# RoboDiscovery-F4_V1_0.net
KiCad netlist of a schematic drawn in EAGLE
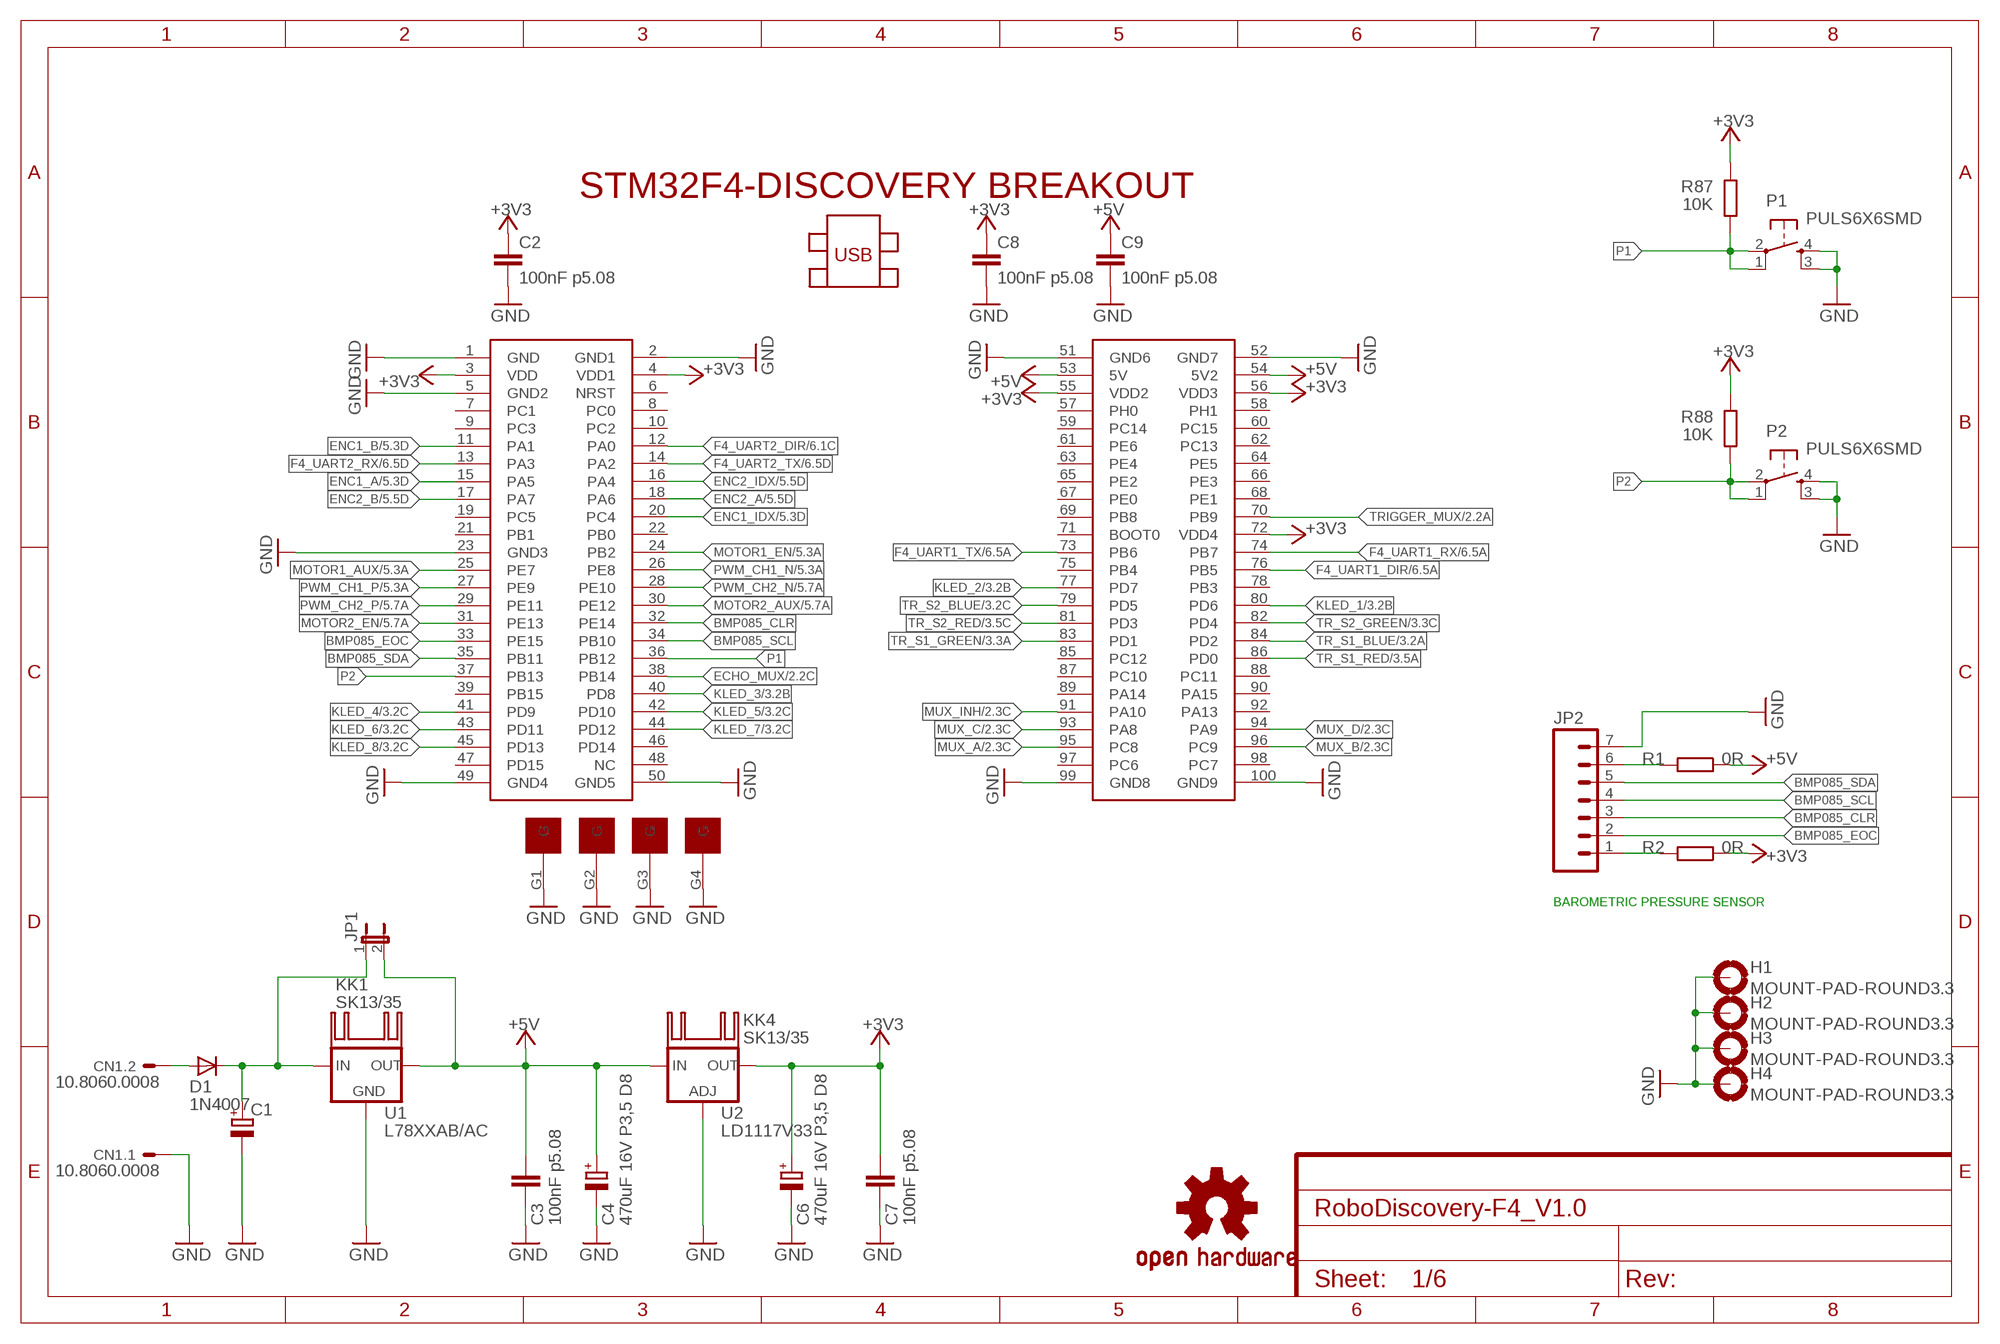
[diagram p0: schematic, sheet 1]
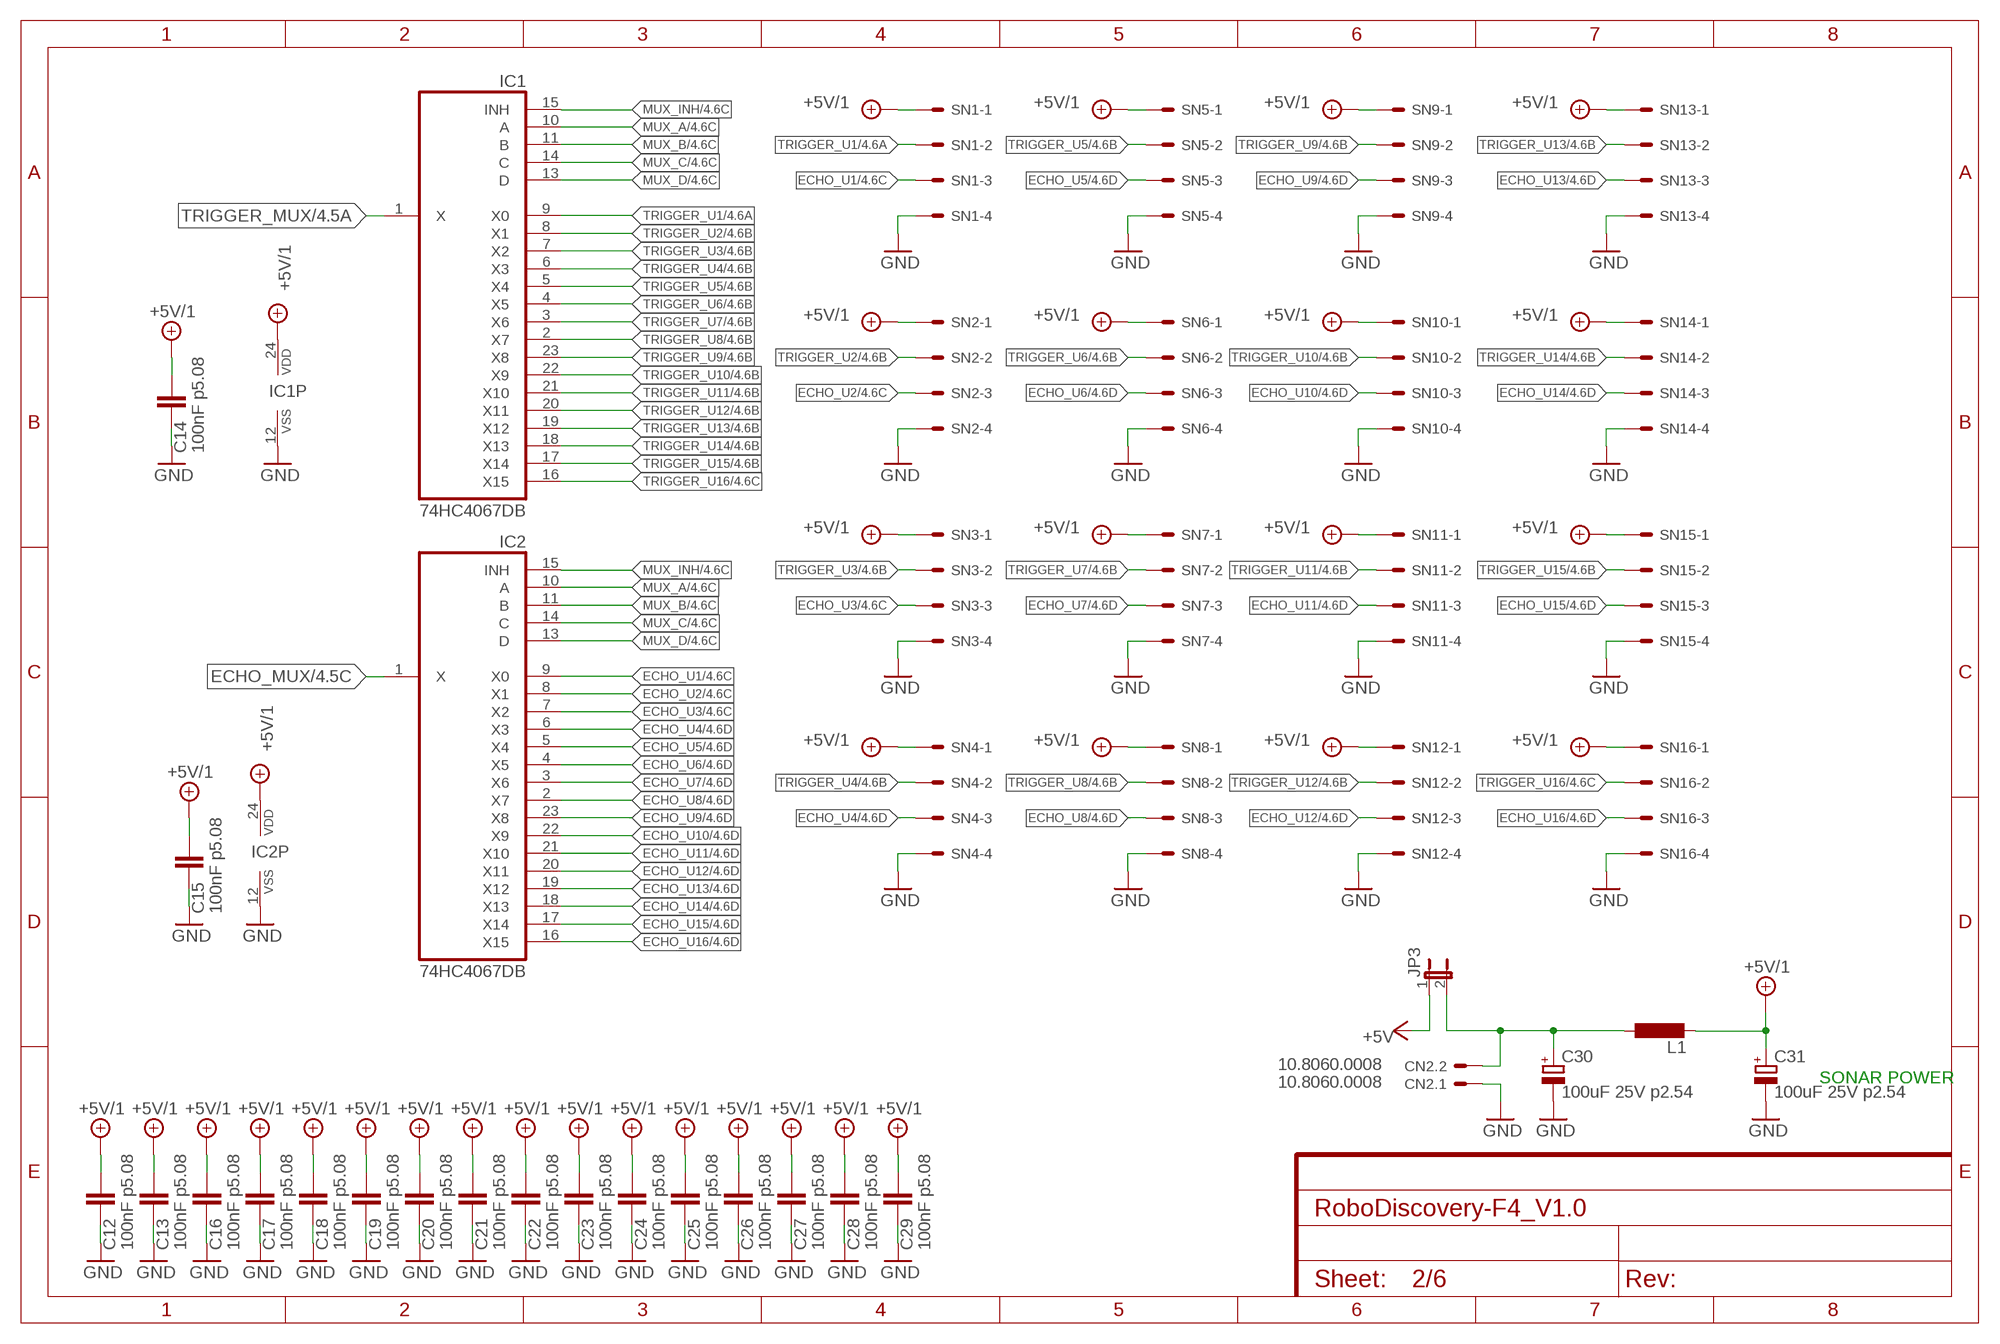
[diagram p1: schematic, sheet 2]
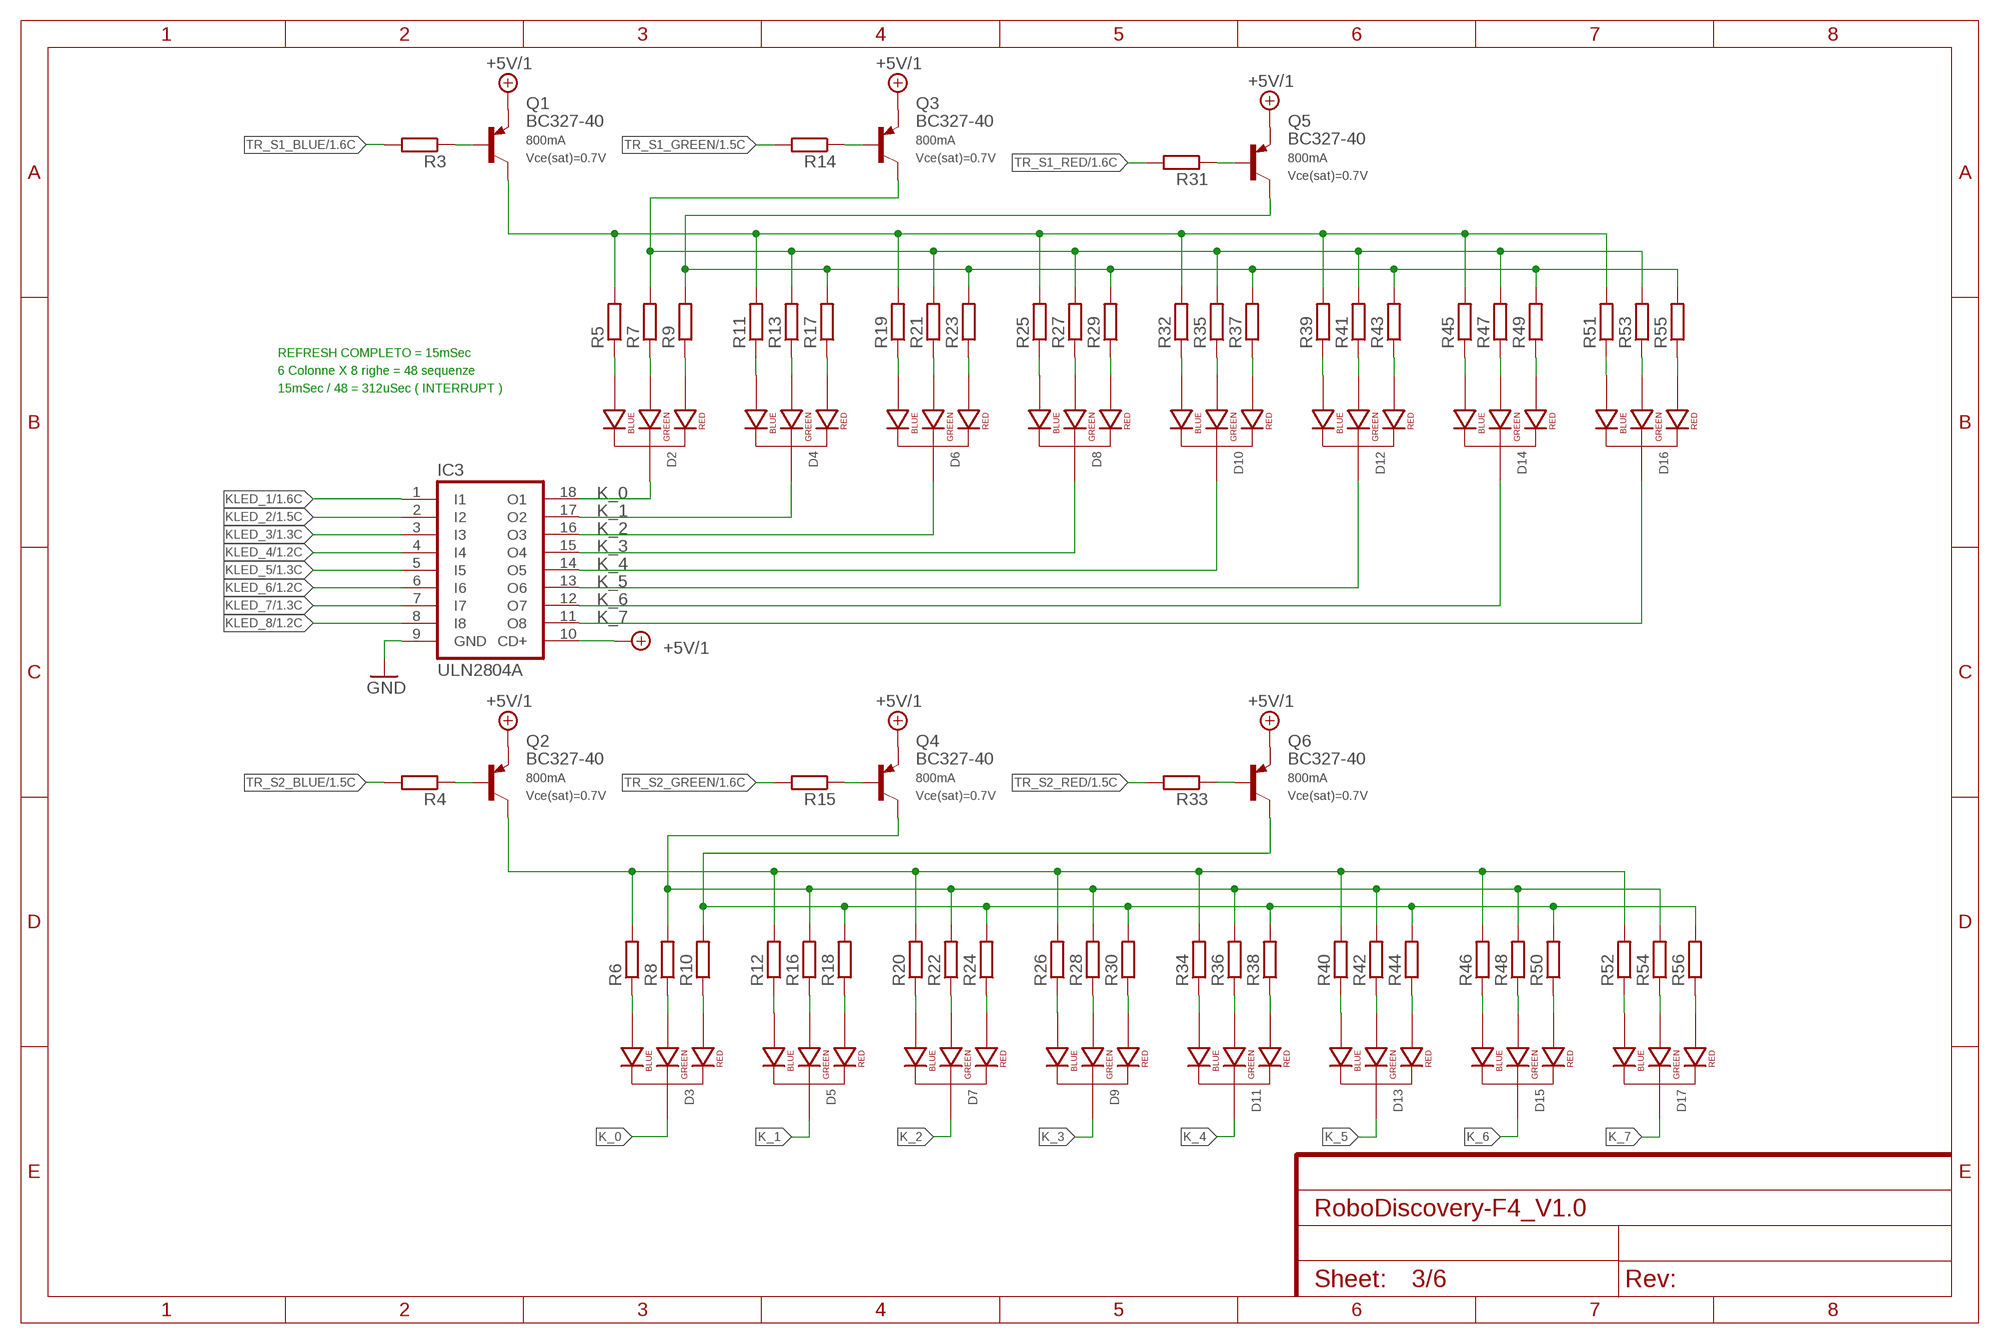
[diagram p2: schematic, sheet 3]
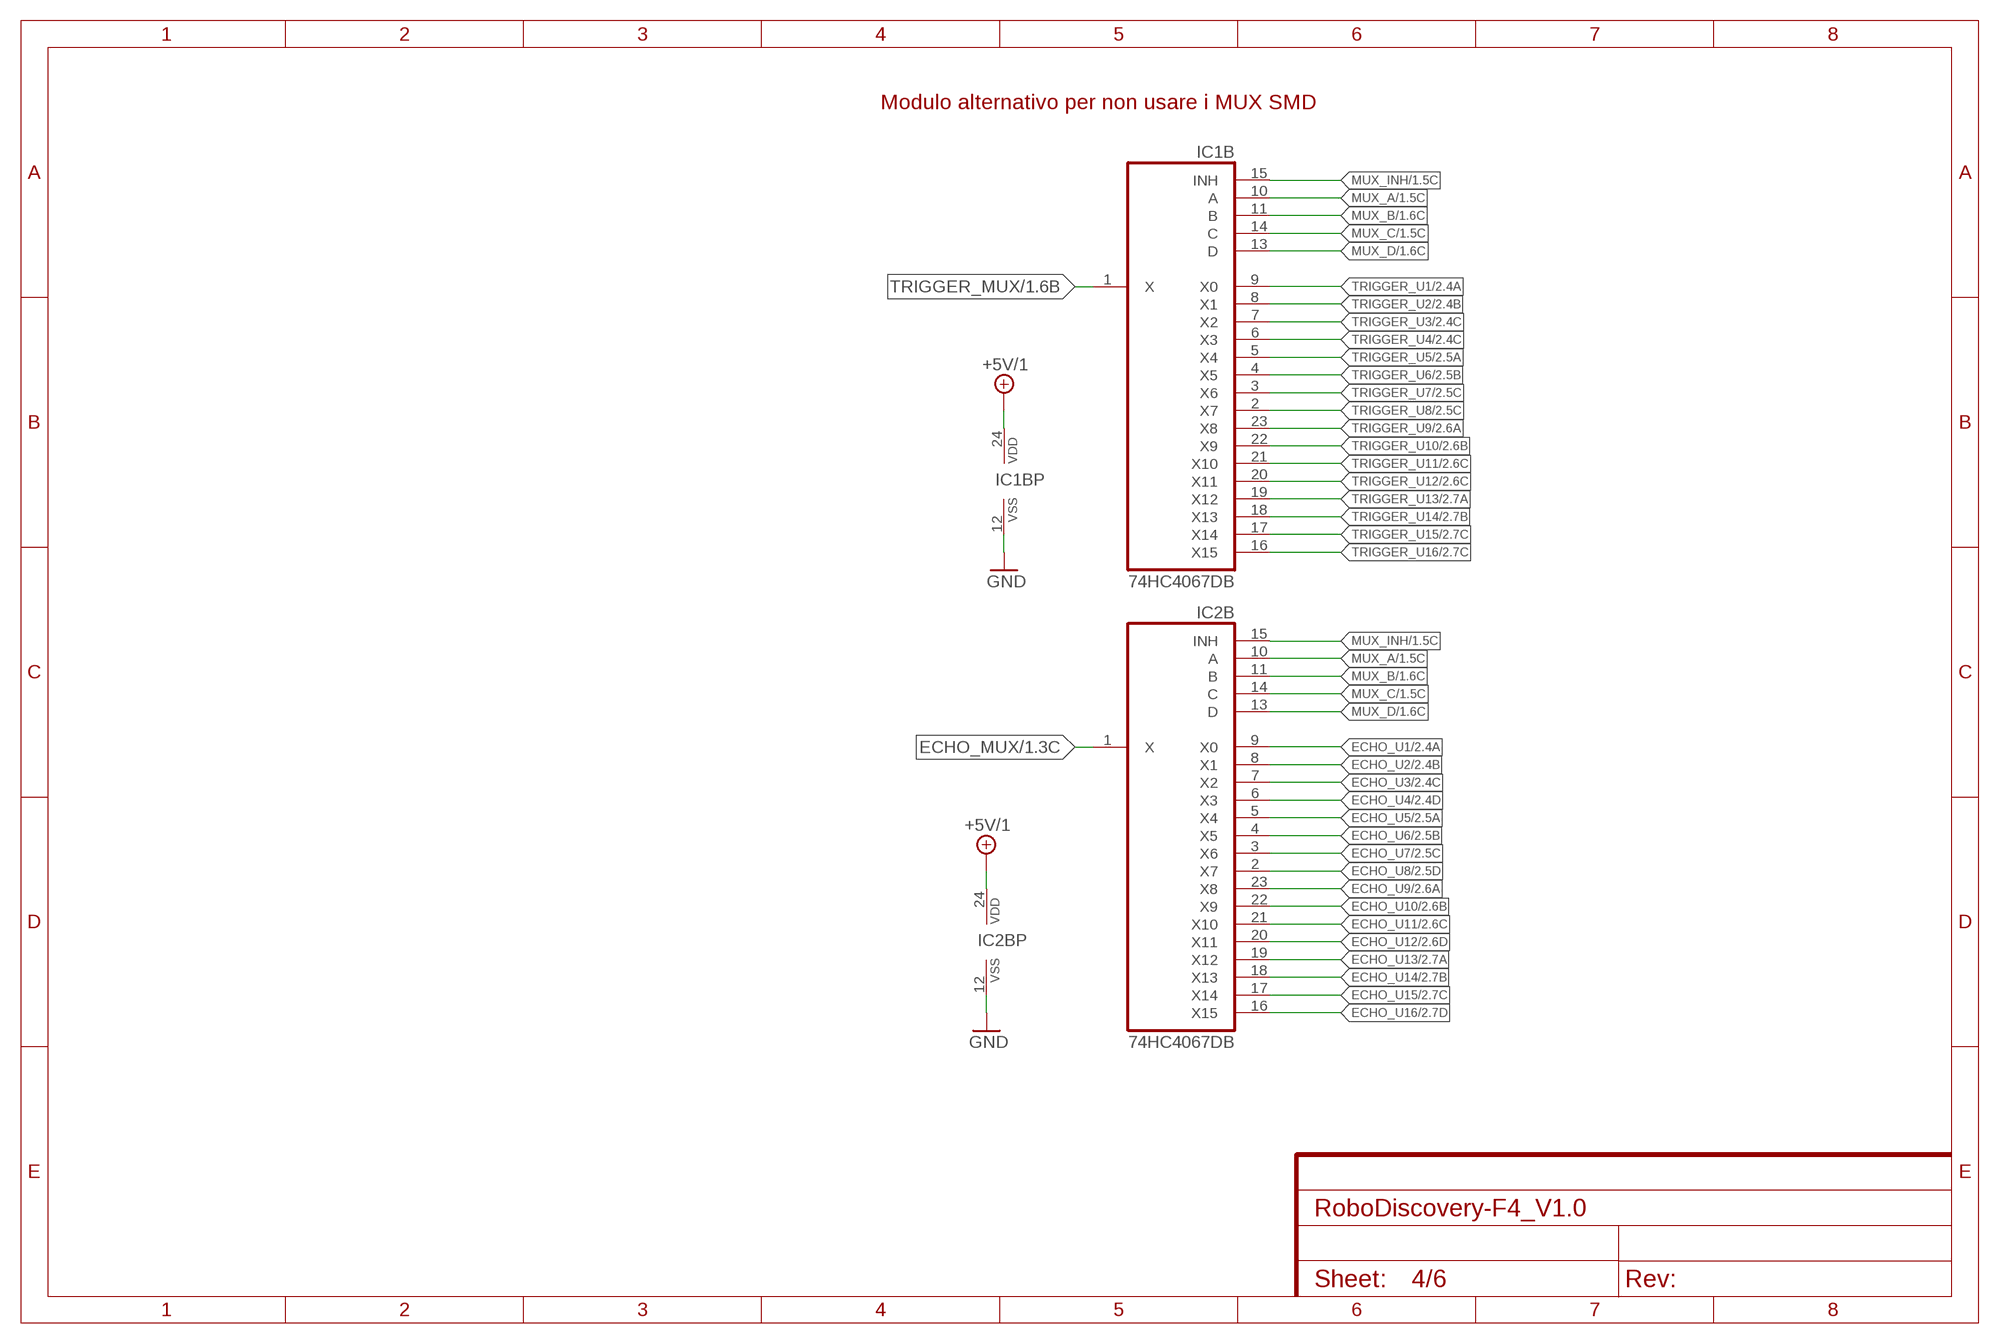
[diagram p3: schematic, sheet 4]
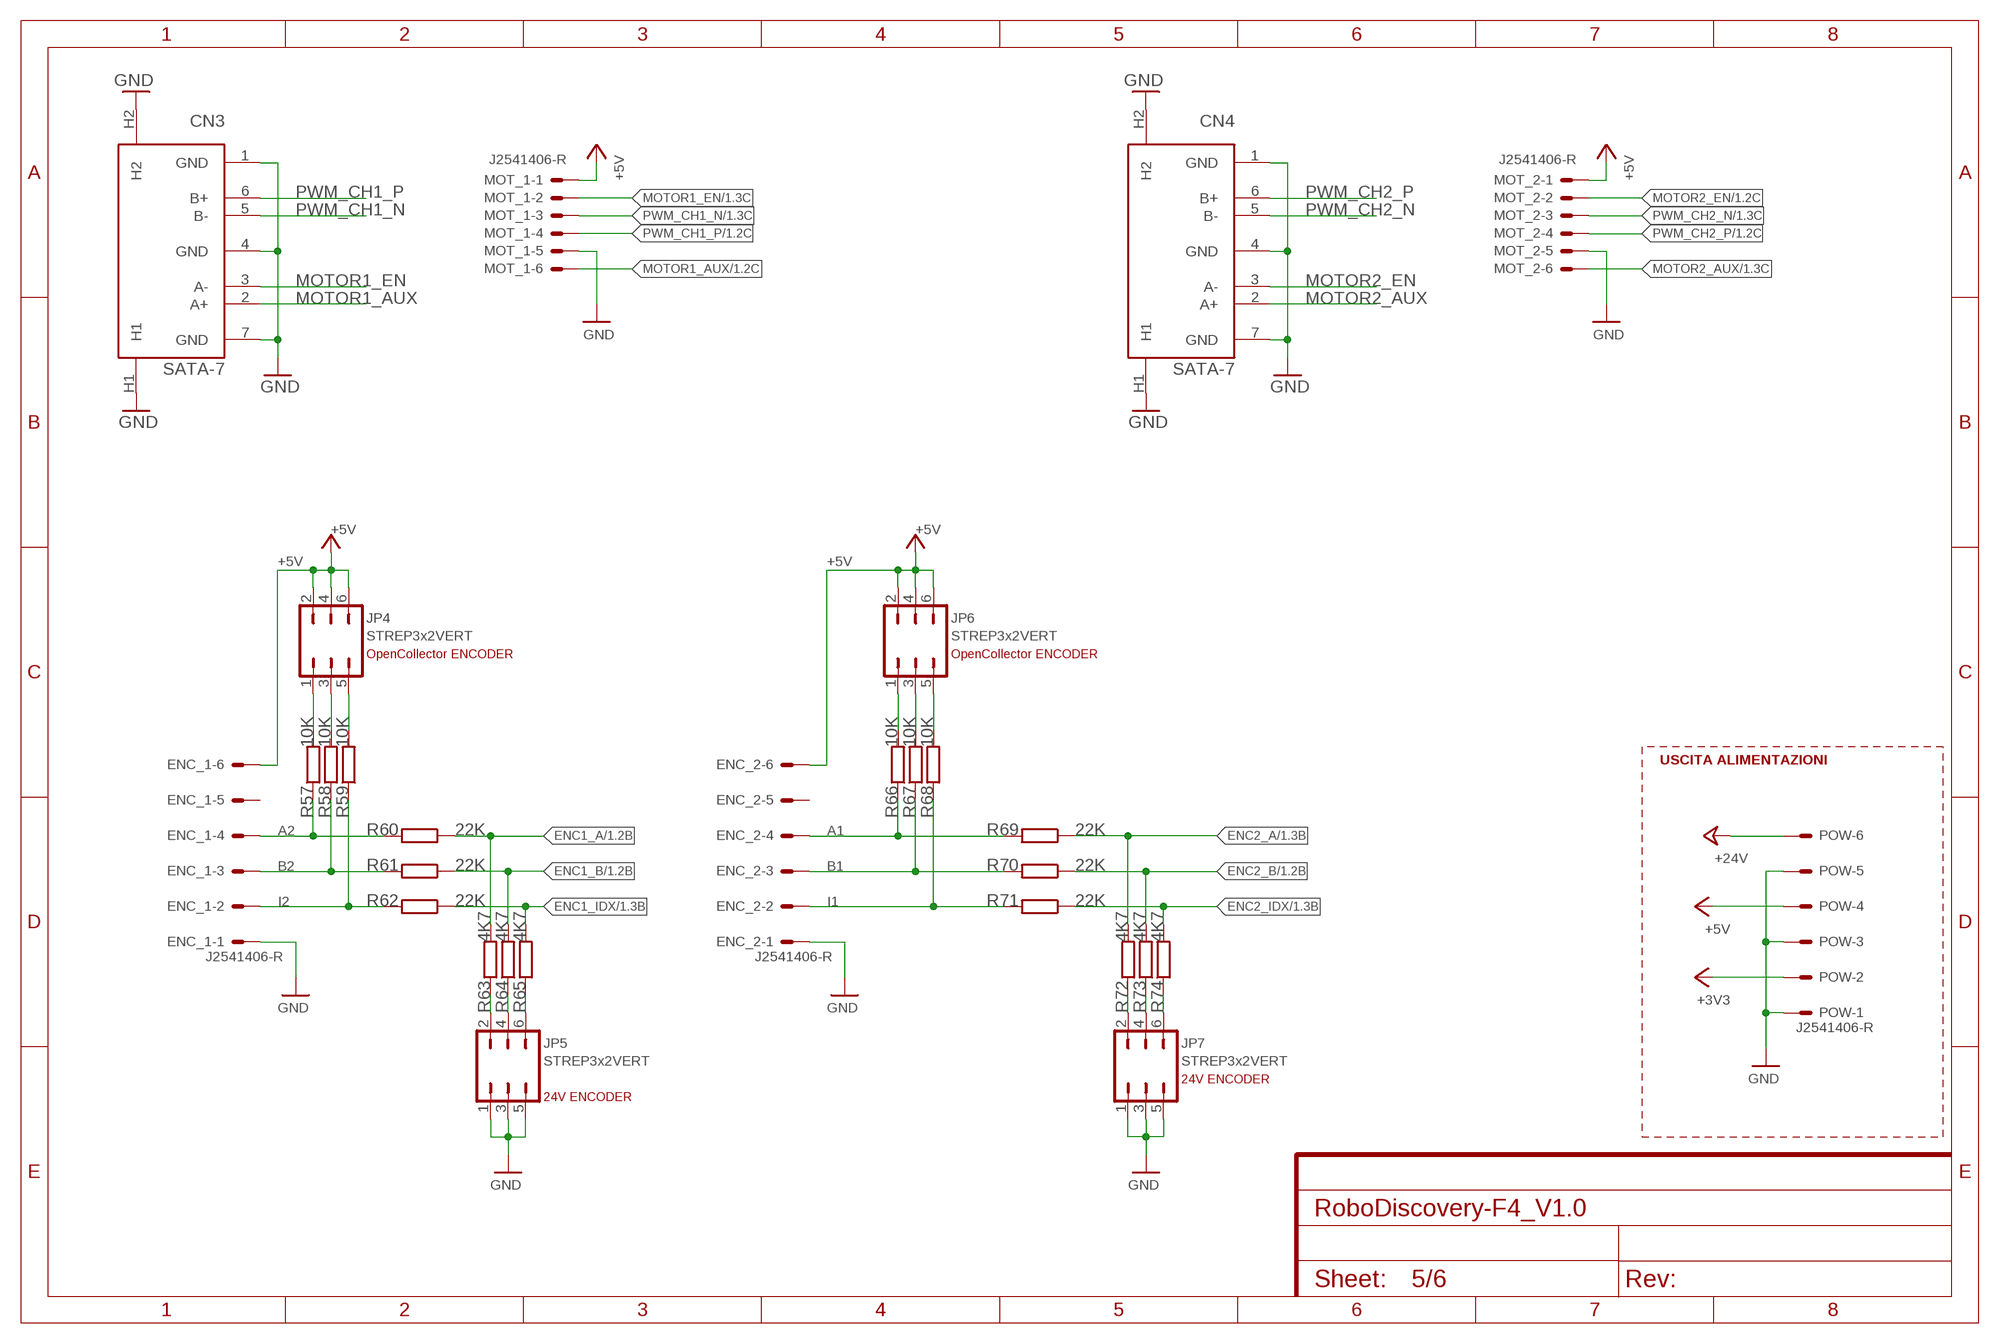
[diagram p4: schematic, sheet 5]
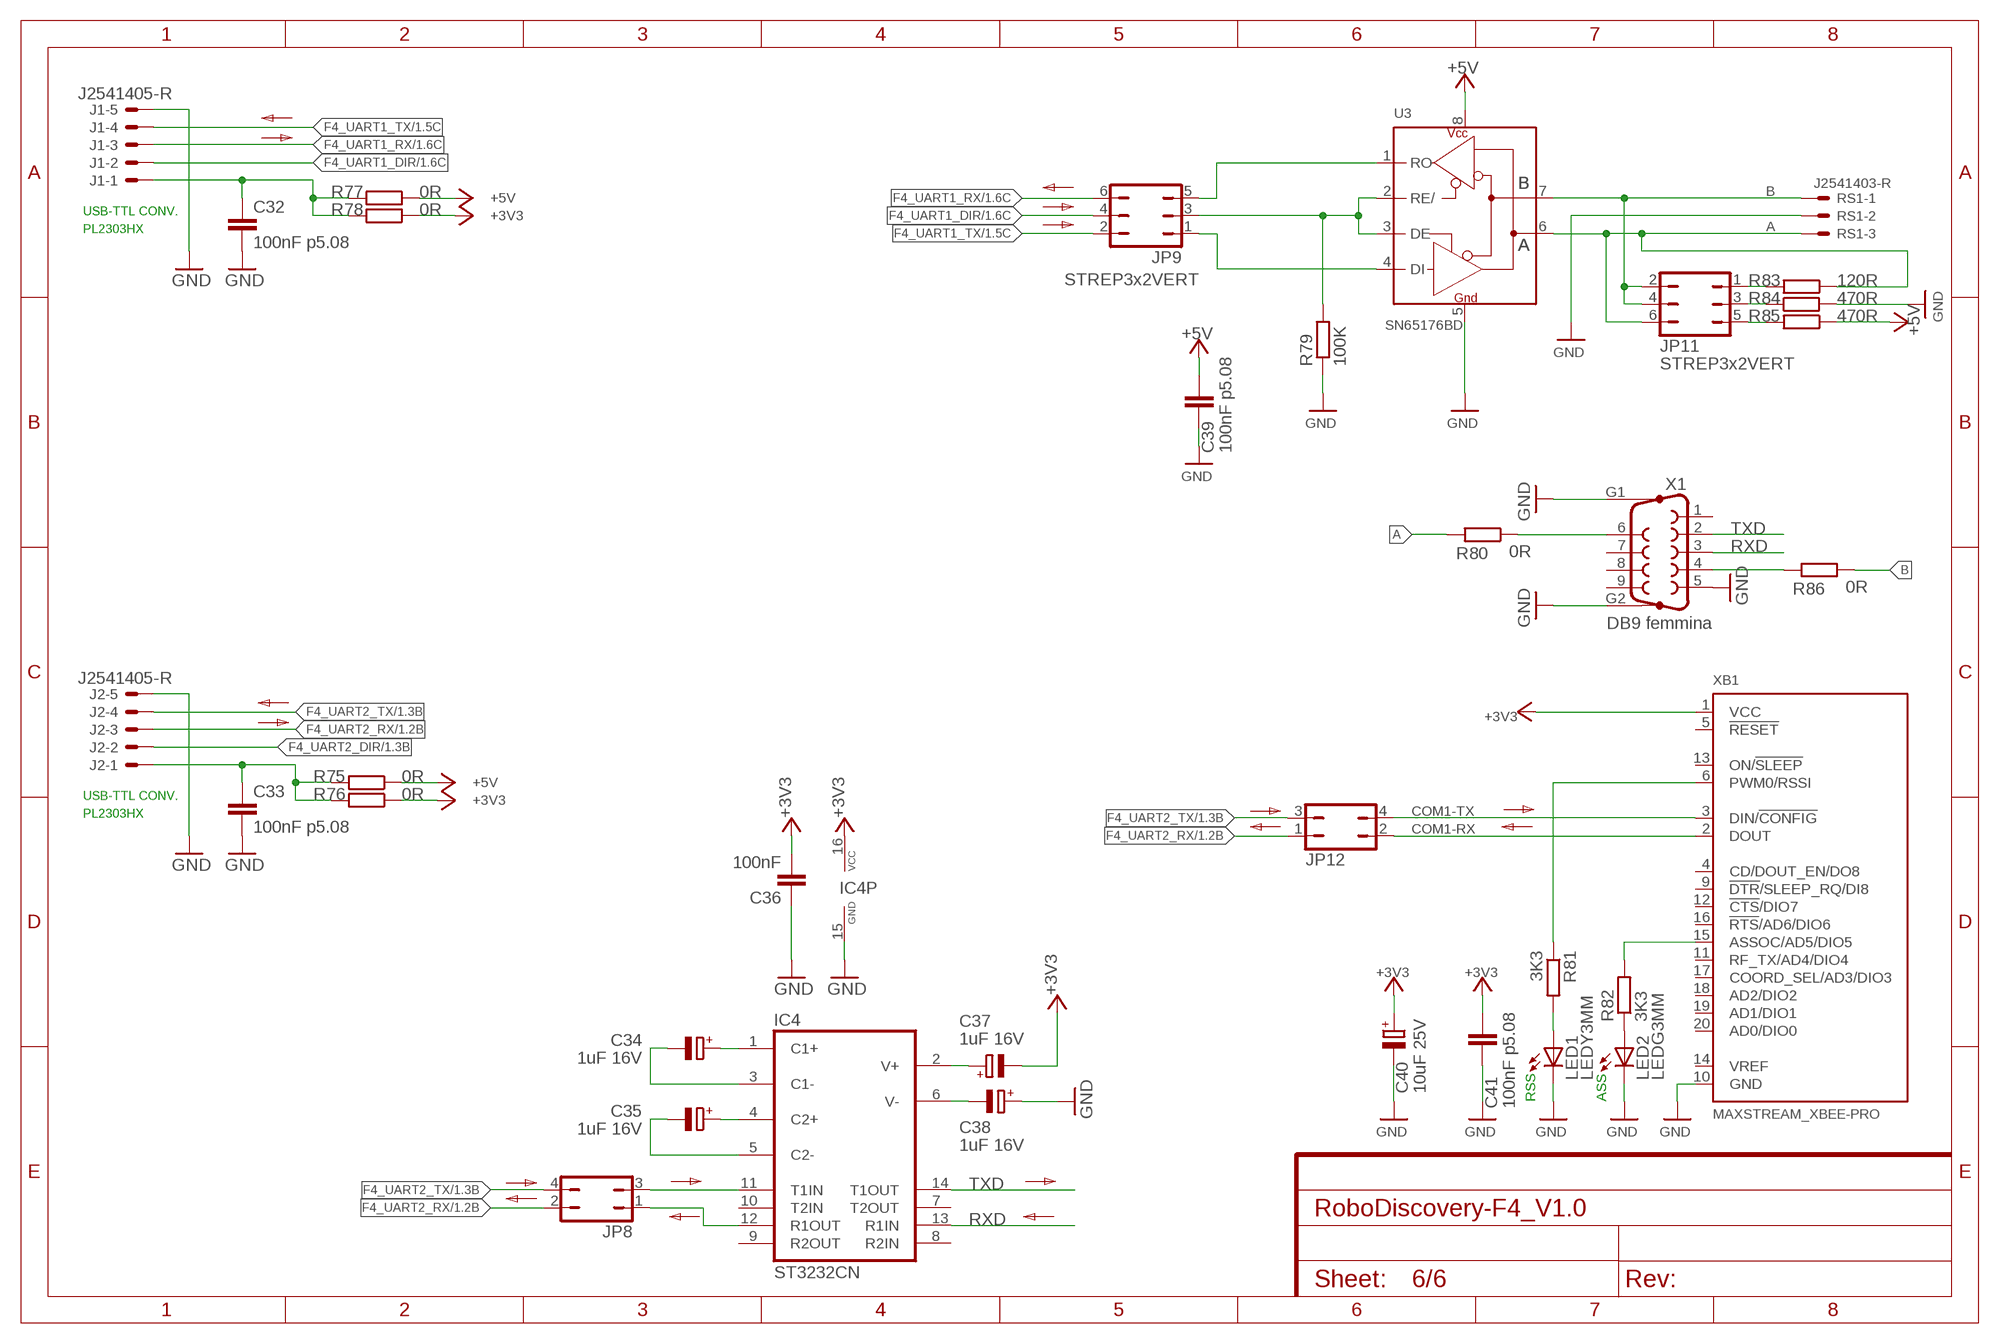
[diagram p5: schematic, sheet 6]

(export (version "E")
  (design (tool "Eeschema 10.0.6"))
  (components
    (comp (ref "D2")
      (value "LED-RGB-CC-THRUDIFFUSE")
      (footprint "eagle-import:LED-RGB-THRU")
      (libsource (lib "eagle-import") (part "LED-RGB-CC-THRUDIFFUSE"))
    )
    (comp (ref "D3")
      (value "LED-RGB-CC-THRUDIFFUSE")
      (footprint "eagle-import:LED-RGB-THRU")
      (libsource (lib "eagle-import") (part "LED-RGB-CC-THRUDIFFUSE"))
    )
    (comp (ref "D4")
      (value "LED-RGB-CC-THRUDIFFUSE")
      (footprint "eagle-import:LED-RGB-THRU")
      (libsource (lib "eagle-import") (part "LED-RGB-CC-THRUDIFFUSE"))
    )
    (comp (ref "D5")
      (value "LED-RGB-CC-THRUDIFFUSE")
      (footprint "eagle-import:LED-RGB-THRU")
      (libsource (lib "eagle-import") (part "LED-RGB-CC-THRUDIFFUSE"))
    )
    (comp (ref "D6")
      (value "LED-RGB-CC-THRUDIFFUSE")
      (footprint "eagle-import:LED-RGB-THRU")
      (libsource (lib "eagle-import") (part "LED-RGB-CC-THRUDIFFUSE"))
    )
    (comp (ref "D7")
      (value "LED-RGB-CC-THRUDIFFUSE")
      (footprint "eagle-import:LED-RGB-THRU")
      (libsource (lib "eagle-import") (part "LED-RGB-CC-THRUDIFFUSE"))
    )
    (comp (ref "D8")
      (value "LED-RGB-CC-THRUDIFFUSE")
      (footprint "eagle-import:LED-RGB-THRU")
      (libsource (lib "eagle-import") (part "LED-RGB-CC-THRUDIFFUSE"))
    )
    (comp (ref "D9")
      (value "LED-RGB-CC-THRUDIFFUSE")
      (footprint "eagle-import:LED-RGB-THRU")
      (libsource (lib "eagle-import") (part "LED-RGB-CC-THRUDIFFUSE"))
    )
    (comp (ref "D10")
      (value "LED-RGB-CC-THRUDIFFUSE")
      (footprint "eagle-import:LED-RGB-THRU")
      (libsource (lib "eagle-import") (part "LED-RGB-CC-THRUDIFFUSE"))
    )
    (comp (ref "D11")
      (value "LED-RGB-CC-THRUDIFFUSE")
      (footprint "eagle-import:LED-RGB-THRU")
      (libsource (lib "eagle-import") (part "LED-RGB-CC-THRUDIFFUSE"))
    )
    (comp (ref "D12")
      (value "LED-RGB-CC-THRUDIFFUSE")
      (footprint "eagle-import:LED-RGB-THRU")
      (libsource (lib "eagle-import") (part "LED-RGB-CC-THRUDIFFUSE"))
    )
    (comp (ref "D13")
      (value "LED-RGB-CC-THRUDIFFUSE")
      (footprint "eagle-import:LED-RGB-THRU")
      (libsource (lib "eagle-import") (part "LED-RGB-CC-THRUDIFFUSE"))
    )
    (comp (ref "D14")
      (value "LED-RGB-CC-THRUDIFFUSE")
      (footprint "eagle-import:LED-RGB-THRU")
      (libsource (lib "eagle-import") (part "LED-RGB-CC-THRUDIFFUSE"))
    )
    (comp (ref "D15")
      (value "LED-RGB-CC-THRUDIFFUSE")
      (footprint "eagle-import:LED-RGB-THRU")
      (libsource (lib "eagle-import") (part "LED-RGB-CC-THRUDIFFUSE"))
    )
    (comp (ref "D16")
      (value "LED-RGB-CC-THRUDIFFUSE")
      (footprint "eagle-import:LED-RGB-THRU")
      (libsource (lib "eagle-import") (part "LED-RGB-CC-THRUDIFFUSE"))
    )
    (comp (ref "D17")
      (value "LED-RGB-CC-THRUDIFFUSE")
      (footprint "eagle-import:LED-RGB-THRU")
      (libsource (lib "eagle-import") (part "LED-RGB-CC-THRUDIFFUSE"))
    )
    (comp (ref "IC3")
      (value "ULN2804A")
      (footprint "eagle-import:DIL18")
      (libsource (lib "eagle-import") (part "ULN2804A"))
    )
    (comp (ref "Q1")
      (value "BC327-40")
      (footprint "eagle-import:TO92-EBC")
      (fields (field (name "I") "800mA") (field (name "VCESAT") "Vce(sat)=0.7V"))
      (libsource (lib "eagle-import") (part "BC327-40"))
    )
    (comp (ref "Q2")
      (value "BC327-40")
      (footprint "eagle-import:TO92-EBC")
      (fields (field (name "I") "800mA") (field (name "VCESAT") "Vce(sat)=0.7V"))
      (libsource (lib "eagle-import") (part "BC327-40"))
    )
    (comp (ref "Q3")
      (value "BC327-40")
      (footprint "eagle-import:TO92-EBC")
      (fields (field (name "I") "800mA") (field (name "VCESAT") "Vce(sat)=0.7V"))
      (libsource (lib "eagle-import") (part "BC327-40"))
    )
    (comp (ref "Q4")
      (value "BC327-40")
      (footprint "eagle-import:TO92-EBC")
      (fields (field (name "I") "800mA") (field (name "VCESAT") "Vce(sat)=0.7V"))
      (libsource (lib "eagle-import") (part "BC327-40"))
    )
    (comp (ref "Q5")
      (value "BC327-40")
      (footprint "eagle-import:TO92-EBC")
      (fields (field (name "I") "800mA") (field (name "VCESAT") "Vce(sat)=0.7V"))
      (libsource (lib "eagle-import") (part "BC327-40"))
    )
    (comp (ref "Q6")
      (value "BC327-40")
      (footprint "eagle-import:TO92-EBC")
      (fields (field (name "I") "800mA") (field (name "VCESAT") "Vce(sat)=0.7V"))
      (libsource (lib "eagle-import") (part "BC327-40"))
    )
    (comp (ref "R3")
      (value "R-EU_0207/7")
      (footprint "eagle-import:0207_7")
      (libsource (lib "eagle-import") (part "R-EU_0207/7"))
    )
    (comp (ref "R4")
      (value "R-EU_0207/7")
      (footprint "eagle-import:0207_7")
      (libsource (lib "eagle-import") (part "R-EU_0207/7"))
    )
    (comp (ref "R5")
      (value "R-EU_0207/7")
      (footprint "eagle-import:0207_7")
      (libsource (lib "eagle-import") (part "R-EU_0207/7"))
    )
    (comp (ref "R6")
      (value "R-EU_0207/7")
      (footprint "eagle-import:0207_7")
      (libsource (lib "eagle-import") (part "R-EU_0207/7"))
    )
    (comp (ref "R7")
      (value "R-EU_0207/7")
      (footprint "eagle-import:0207_7")
      (libsource (lib "eagle-import") (part "R-EU_0207/7"))
    )
    (comp (ref "R8")
      (value "R-EU_0207/7")
      (footprint "eagle-import:0207_7")
      (libsource (lib "eagle-import") (part "R-EU_0207/7"))
    )
    (comp (ref "R9")
      (value "R-EU_0207/7")
      (footprint "eagle-import:0207_7")
      (libsource (lib "eagle-import") (part "R-EU_0207/7"))
    )
    (comp (ref "R10")
      (value "R-EU_0207/7")
      (footprint "eagle-import:0207_7")
      (libsource (lib "eagle-import") (part "R-EU_0207/7"))
    )
    (comp (ref "R11")
      (value "R-EU_0207/7")
      (footprint "eagle-import:0207_7")
      (libsource (lib "eagle-import") (part "R-EU_0207/7"))
    )
    (comp (ref "R12")
      (value "R-EU_0207/7")
      (footprint "eagle-import:0207_7")
      (libsource (lib "eagle-import") (part "R-EU_0207/7"))
    )
    (comp (ref "R13")
      (value "R-EU_0207/7")
      (footprint "eagle-import:0207_7")
      (libsource (lib "eagle-import") (part "R-EU_0207/7"))
    )
    (comp (ref "R14")
      (value "R-EU_0207/7")
      (footprint "eagle-import:0207_7")
      (libsource (lib "eagle-import") (part "R-EU_0207/7"))
    )
    (comp (ref "R15")
      (value "R-EU_0207/7")
      (footprint "eagle-import:0207_7")
      (libsource (lib "eagle-import") (part "R-EU_0207/7"))
    )
    (comp (ref "R16")
      (value "R-EU_0207/7")
      (footprint "eagle-import:0207_7")
      (libsource (lib "eagle-import") (part "R-EU_0207/7"))
    )
    (comp (ref "R17")
      (value "R-EU_0207/7")
      (footprint "eagle-import:0207_7")
      (libsource (lib "eagle-import") (part "R-EU_0207/7"))
    )
    (comp (ref "R18")
      (value "R-EU_0207/7")
      (footprint "eagle-import:0207_7")
      (libsource (lib "eagle-import") (part "R-EU_0207/7"))
    )
    (comp (ref "R19")
      (value "R-EU_0207/7")
      (footprint "eagle-import:0207_7")
      (libsource (lib "eagle-import") (part "R-EU_0207/7"))
    )
    (comp (ref "R20")
      (value "R-EU_0207/7")
      (footprint "eagle-import:0207_7")
      (libsource (lib "eagle-import") (part "R-EU_0207/7"))
    )
    (comp (ref "R21")
      (value "R-EU_0207/7")
      (footprint "eagle-import:0207_7")
      (libsource (lib "eagle-import") (part "R-EU_0207/7"))
    )
    (comp (ref "R22")
      (value "R-EU_0207/7")
      (footprint "eagle-import:0207_7")
      (libsource (lib "eagle-import") (part "R-EU_0207/7"))
    )
    (comp (ref "R23")
      (value "R-EU_0207/7")
      (footprint "eagle-import:0207_7")
      (libsource (lib "eagle-import") (part "R-EU_0207/7"))
    )
    (comp (ref "R24")
      (value "R-EU_0207/7")
      (footprint "eagle-import:0207_7")
      (libsource (lib "eagle-import") (part "R-EU_0207/7"))
    )
    (comp (ref "R25")
      (value "R-EU_0207/7")
      (footprint "eagle-import:0207_7")
      (libsource (lib "eagle-import") (part "R-EU_0207/7"))
    )
    (comp (ref "R26")
      (value "R-EU_0207/7")
      (footprint "eagle-import:0207_7")
      (libsource (lib "eagle-import") (part "R-EU_0207/7"))
    )
    (comp (ref "R27")
      (value "R-EU_0207/7")
      (footprint "eagle-import:0207_7")
      (libsource (lib "eagle-import") (part "R-EU_0207/7"))
    )
    (comp (ref "R28")
      (value "R-EU_0207/7")
      (footprint "eagle-import:0207_7")
      (libsource (lib "eagle-import") (part "R-EU_0207/7"))
    )
    (comp (ref "R29")
      (value "R-EU_0207/7")
      (footprint "eagle-import:0207_7")
      (libsource (lib "eagle-import") (part "R-EU_0207/7"))
    )
    (comp (ref "R30")
      (value "R-EU_0207/7")
      (footprint "eagle-import:0207_7")
      (libsource (lib "eagle-import") (part "R-EU_0207/7"))
    )
    (comp (ref "R31")
      (value "R-EU_0207/7")
      (footprint "eagle-import:0207_7")
      (libsource (lib "eagle-import") (part "R-EU_0207/7"))
    )
    (comp (ref "R32")
      (value "R-EU_0207/7")
      (footprint "eagle-import:0207_7")
      (libsource (lib "eagle-import") (part "R-EU_0207/7"))
    )
    (comp (ref "R33")
      (value "R-EU_0207/7")
      (footprint "eagle-import:0207_7")
      (libsource (lib "eagle-import") (part "R-EU_0207/7"))
    )
    (comp (ref "R34")
      (value "R-EU_0207/7")
      (footprint "eagle-import:0207_7")
      (libsource (lib "eagle-import") (part "R-EU_0207/7"))
    )
    (comp (ref "R35")
      (value "R-EU_0207/7")
      (footprint "eagle-import:0207_7")
      (libsource (lib "eagle-import") (part "R-EU_0207/7"))
    )
    (comp (ref "R36")
      (value "R-EU_0207/7")
      (footprint "eagle-import:0207_7")
      (libsource (lib "eagle-import") (part "R-EU_0207/7"))
    )
    (comp (ref "R37")
      (value "R-EU_0207/7")
      (footprint "eagle-import:0207_7")
      (libsource (lib "eagle-import") (part "R-EU_0207/7"))
    )
    (comp (ref "R38")
      (value "R-EU_0207/7")
      (footprint "eagle-import:0207_7")
      (libsource (lib "eagle-import") (part "R-EU_0207/7"))
    )
    (comp (ref "R39")
      (value "R-EU_0207/7")
      (footprint "eagle-import:0207_7")
      (libsource (lib "eagle-import") (part "R-EU_0207/7"))
    )
    (comp (ref "R40")
      (value "R-EU_0207/7")
      (footprint "eagle-import:0207_7")
      (libsource (lib "eagle-import") (part "R-EU_0207/7"))
    )
    (comp (ref "R41")
      (value "R-EU_0207/7")
      (footprint "eagle-import:0207_7")
      (libsource (lib "eagle-import") (part "R-EU_0207/7"))
    )
    (comp (ref "R42")
      (value "R-EU_0207/7")
      (footprint "eagle-import:0207_7")
      (libsource (lib "eagle-import") (part "R-EU_0207/7"))
    )
    (comp (ref "R43")
      (value "R-EU_0207/7")
      (footprint "eagle-import:0207_7")
      (libsource (lib "eagle-import") (part "R-EU_0207/7"))
    )
    (comp (ref "R44")
      (value "R-EU_0207/7")
      (footprint "eagle-import:0207_7")
      (libsource (lib "eagle-import") (part "R-EU_0207/7"))
    )
    (comp (ref "R45")
      (value "R-EU_0207/7")
      (footprint "eagle-import:0207_7")
      (libsource (lib "eagle-import") (part "R-EU_0207/7"))
    )
    (comp (ref "R46")
      (value "R-EU_0207/7")
      (footprint "eagle-import:0207_7")
      (libsource (lib "eagle-import") (part "R-EU_0207/7"))
    )
    (comp (ref "R47")
      (value "R-EU_0207/7")
      (footprint "eagle-import:0207_7")
      (libsource (lib "eagle-import") (part "R-EU_0207/7"))
    )
    (comp (ref "R48")
      (value "R-EU_0207/7")
      (footprint "eagle-import:0207_7")
      (libsource (lib "eagle-import") (part "R-EU_0207/7"))
    )
    (comp (ref "R49")
      (value "R-EU_0207/7")
      (footprint "eagle-import:0207_7")
      (libsource (lib "eagle-import") (part "R-EU_0207/7"))
    )
    (comp (ref "R50")
      (value "R-EU_0207/7")
      (footprint "eagle-import:0207_7")
      (libsource (lib "eagle-import") (part "R-EU_0207/7"))
    )
    (comp (ref "R51")
      (value "R-EU_0207/7")
      (footprint "eagle-import:0207_7")
      (libsource (lib "eagle-import") (part "R-EU_0207/7"))
    )
    (comp (ref "R52")
      (value "R-EU_0207/7")
      (footprint "eagle-import:0207_7")
      (libsource (lib "eagle-import") (part "R-EU_0207/7"))
    )
    (comp (ref "R53")
      (value "R-EU_0207/7")
      (footprint "eagle-import:0207_7")
      (libsource (lib "eagle-import") (part "R-EU_0207/7"))
    )
    (comp (ref "R54")
      (value "R-EU_0207/7")
      (footprint "eagle-import:0207_7")
      (libsource (lib "eagle-import") (part "R-EU_0207/7"))
    )
    (comp (ref "R55")
      (value "R-EU_0207/7")
      (footprint "eagle-import:0207_7")
      (libsource (lib "eagle-import") (part "R-EU_0207/7"))
    )
    (comp (ref "R56")
      (value "R-EU_0207/7")
      (footprint "eagle-import:0207_7")
      (libsource (lib "eagle-import") (part "R-EU_0207/7"))
    )
    (comp (ref "C1")
      (value "CPOL-EUE5-13")
      (footprint "eagle-import:E5-13")
      (libsource (lib "eagle-import") (part "CPOL-EUE5-13"))
    )
    (comp (ref "C2")
      (value "100nF p5.08")
      (footprint "eagle-import:C050-024X044")
      (libsource (lib "eagle-import") (part "C-EU050-024X044"))
    )
    (comp (ref "C3")
      (value "100nF p5.08")
      (footprint "eagle-import:C050-024X044")
      (libsource (lib "eagle-import") (part "C-EU050-024X044"))
    )
    (comp (ref "C4")
      (value "470uF 16V P3,5 D8")
      (footprint "eagle-import:E3,5-8")
      (libsource (lib "eagle-import") (part "CPOL-EUE3.5-8"))
    )
    (comp (ref "C6")
      (value "470uF 16V P3,5 D8")
      (footprint "eagle-import:E3,5-8")
      (libsource (lib "eagle-import") (part "CPOL-EUE3.5-8"))
    )
    (comp (ref "C7")
      (value "100nF p5.08")
      (footprint "eagle-import:C050-024X044")
      (libsource (lib "eagle-import") (part "C-EU050-024X044"))
    )
    (comp (ref "C8")
      (value "100nF p5.08")
      (footprint "eagle-import:C050-024X044")
      (libsource (lib "eagle-import") (part "C-EU050-024X044"))
    )
    (comp (ref "C9")
      (value "100nF p5.08")
      (footprint "eagle-import:C050-024X044")
      (libsource (lib "eagle-import") (part "C-EU050-024X044"))
    )
    (comp (ref "CN1")
      (value "10.8060.0008")
      (footprint "eagle-import:300-021-13_2P_5VE")
      (libsource (lib "eagle-import") (part "10.8060.0008"))
    )
    (comp (ref "D1")
      (value "1N4007")
      (footprint "eagle-import:D041-10")
      (libsource (lib "eagle-import") (part "1N4007"))
    )
    (comp (ref "DIS1")
      (value "STM32F4-DISCOVERY")
      (footprint "eagle-import:STM32F4-DISCOVERY")
      (libsource (lib "eagle-import") (part "STM32F4-DISCOVERY"))
    )
    (comp (ref "H1")
      (value "MOUNT-PAD-ROUND3.3")
      (footprint "eagle-import:3,3-PAD")
      (libsource (lib "eagle-import") (part "MOUNT-PAD-ROUND3.3"))
    )
    (comp (ref "H2")
      (value "MOUNT-PAD-ROUND3.3")
      (footprint "eagle-import:3,3-PAD")
      (libsource (lib "eagle-import") (part "MOUNT-PAD-ROUND3.3"))
    )
    (comp (ref "H3")
      (value "MOUNT-PAD-ROUND3.3")
      (footprint "eagle-import:3,3-PAD")
      (libsource (lib "eagle-import") (part "MOUNT-PAD-ROUND3.3"))
    )
    (comp (ref "H4")
      (value "MOUNT-PAD-ROUND3.3")
      (footprint "eagle-import:3,3-PAD")
      (libsource (lib "eagle-import") (part "MOUNT-PAD-ROUND3.3"))
    )
    (comp (ref "JP1")
      (value "JP1E")
      (footprint "eagle-import:JP1")
      (libsource (lib "eagle-import") (part "JP1E"))
    )
    (comp (ref "JP2")
      (value "M07LONGPADS")
      (footprint "eagle-import:1X07_LONGPADS")
      (libsource (lib "eagle-import") (part "M07LONGPADS"))
    )
    (comp (ref "KK1")
      (value "SK13/35")
      (footprint "eagle-import:SK13_35")
      (libsource (lib "eagle-import") (part "SK13/35"))
    )
    (comp (ref "KK4")
      (value "SK13/35")
      (footprint "eagle-import:SK13_35")
      (libsource (lib "eagle-import") (part "SK13/35"))
    )
    (comp (ref "LOGO1")
      (value "OSHW-LOGOM")
      (footprint "eagle-import:OSHW-LOGO-M")
      (libsource (lib "eagle-import") (part "OSHW-LOGOM"))
    )
    (comp (ref "P1")
      (value "PULS6X6SMD")
      (footprint "eagle-import:PULS6X6SMD")
      (libsource (lib "eagle-import") (part "PULS6X6SMD"))
    )
    (comp (ref "P2")
      (value "PULS6X6SMD")
      (footprint "eagle-import:PULS6X6SMD")
      (libsource (lib "eagle-import") (part "PULS6X6SMD"))
    )
    (comp (ref "R1")
      (value "0R")
      (footprint "eagle-import:0207_7")
      (libsource (lib "eagle-import") (part "R-EU_0207/7"))
    )
    (comp (ref "R2")
      (value "0R")
      (footprint "eagle-import:0207_7")
      (libsource (lib "eagle-import") (part "R-EU_0207/7"))
    )
    (comp (ref "R87")
      (value "10K")
      (footprint "eagle-import:0207_7")
      (libsource (lib "eagle-import") (part "R-EU_0207/7"))
    )
    (comp (ref "R88")
      (value "10K")
      (footprint "eagle-import:0207_7")
      (libsource (lib "eagle-import") (part "R-EU_0207/7"))
    )
    (comp (ref "U1")
      (value "L78XXAB/AC")
      (footprint "eagle-import:78XXL")
      (libsource (lib "eagle-import") (part "L78XXAB/AC"))
    )
    (comp (ref "U2")
      (value "LD1117V33")
      (footprint "eagle-import:317TL")
      (libsource (lib "eagle-import") (part "LM317TL"))
    )
    (comp (ref "IC1B")
      (value "74HC4067DB")
      (footprint "eagle-import:DIL24-6")
      (libsource (lib "eagle-import") (part "4067N"))
    )
    (comp (ref "IC2B")
      (value "74HC4067DB")
      (footprint "eagle-import:DIL24-6")
      (libsource (lib "eagle-import") (part "4067N"))
    )
    (comp (ref "C32")
      (value "100nF p5.08")
      (footprint "eagle-import:C050-024X044")
      (libsource (lib "eagle-import") (part "C-EU050-024X044"))
    )
    (comp (ref "C33")
      (value "100nF p5.08")
      (footprint "eagle-import:C050-024X044")
      (libsource (lib "eagle-import") (part "C-EU050-024X044"))
    )
    (comp (ref "C34")
      (value "1uF 16V")
      (footprint "eagle-import:E2,5-5")
      (libsource (lib "eagle-import") (part "CPOL-EUE2.5-5"))
    )
    (comp (ref "C35")
      (value "1uF 16V")
      (footprint "eagle-import:E2,5-5")
      (libsource (lib "eagle-import") (part "CPOL-EUE2.5-5"))
    )
    (comp (ref "C36")
      (value "100nF")
      (footprint "eagle-import:C025-025X050")
      (libsource (lib "eagle-import") (part "C-EU025-025X050"))
    )
    (comp (ref "C37")
      (value "1uF 16V")
      (footprint "eagle-import:E2,5-5")
      (libsource (lib "eagle-import") (part "CPOL-EUE2.5-5"))
    )
    (comp (ref "C38")
      (value "1uF 16V")
      (footprint "eagle-import:E2,5-5")
      (libsource (lib "eagle-import") (part "CPOL-EUE2.5-5"))
    )
    (comp (ref "C39")
      (value "100nF p5.08")
      (footprint "eagle-import:C050-024X044")
      (libsource (lib "eagle-import") (part "C-EU050-024X044"))
    )
    (comp (ref "C40")
      (value "10uF 25V")
      (footprint "eagle-import:E2,5-5")
      (libsource (lib "eagle-import") (part "CPOL-EUE2.5-5"))
    )
    (comp (ref "C41")
      (value "100nF p5.08")
      (footprint "eagle-import:C050-024X044")
      (libsource (lib "eagle-import") (part "C-EU050-024X044"))
    )
    (comp (ref "IC4")
      (value "ST3232CN")
      (footprint "eagle-import:DIL16")
      (fields (field (name "MF") "MAXIM") (field (name "MPN") "MAX232ACPE+"))
      (libsource (lib "eagle-import") (part "MAX232"))
    )
    (comp (ref "J1")
      (value "J2541405-R")
      (footprint "eagle-import:6410-05")
      (libsource (lib "eagle-import") (part "22-?-0527-2051"))
    )
    (comp (ref "J2")
      (value "J2541405-R")
      (footprint "eagle-import:6410-05")
      (libsource (lib "eagle-import") (part "22-?-0527-2051"))
    )
    (comp (ref "JP8")
      (value "JP2Q")
      (footprint "eagle-import:JP2Q")
      (libsource (lib "eagle-import") (part "JP2Q"))
    )
    (comp (ref "JP9")
      (value "STREP3x2VERT")
      (footprint "eagle-import:JP3Q")
      (libsource (lib "eagle-import") (part "JP3Q"))
    )
    (comp (ref "JP11")
      (value "STREP3x2VERT")
      (footprint "eagle-import:JP3Q")
      (libsource (lib "eagle-import") (part "JP3Q"))
    )
    (comp (ref "JP12")
      (value "JP2Q")
      (footprint "eagle-import:JP2Q")
      (libsource (lib "eagle-import") (part "JP2Q"))
    )
    (comp (ref "LED1")
      (value "LEDY3MM")
      (footprint "eagle-import:LED3MM")
      (libsource (lib "eagle-import") (part "LED3MM"))
    )
    (comp (ref "LED2")
      (value "LEDG3MM")
      (footprint "eagle-import:LED3MM")
      (libsource (lib "eagle-import") (part "LED3MM"))
    )
    (comp (ref "R75")
      (value "0R")
      (footprint "eagle-import:0207_7")
      (libsource (lib "eagle-import") (part "R-EU_0207/7"))
    )
    (comp (ref "R76")
      (value "0R")
      (footprint "eagle-import:0207_7")
      (libsource (lib "eagle-import") (part "R-EU_0207/7"))
    )
    (comp (ref "R77")
      (value "0R")
      (footprint "eagle-import:0207_7")
      (libsource (lib "eagle-import") (part "R-EU_0207/7"))
    )
    (comp (ref "R78")
      (value "0R")
      (footprint "eagle-import:0207_7")
      (libsource (lib "eagle-import") (part "R-EU_0207/7"))
    )
    (comp (ref "R79")
      (value "100K")
      (footprint "eagle-import:0207_7")
      (libsource (lib "eagle-import") (part "R-EU_0207/7"))
    )
    (comp (ref "R80")
      (value "0R")
      (footprint "eagle-import:0207_7")
      (libsource (lib "eagle-import") (part "R-EU_0207/7"))
    )
    (comp (ref "R81")
      (value "3K3")
      (footprint "eagle-import:0207_7")
      (libsource (lib "eagle-import") (part "R-EU_0207/7"))
    )
    (comp (ref "R82")
      (value "3K3")
      (footprint "eagle-import:0207_7")
      (libsource (lib "eagle-import") (part "R-EU_0207/7"))
    )
    (comp (ref "R83")
      (value "120R")
      (footprint "eagle-import:0207_7")
      (libsource (lib "eagle-import") (part "R-EU_0207/7"))
    )
    (comp (ref "R84")
      (value "470R")
      (footprint "eagle-import:0207_7")
      (libsource (lib "eagle-import") (part "R-EU_0207/7"))
    )
    (comp (ref "R85")
      (value "470R")
      (footprint "eagle-import:0207_7")
      (libsource (lib "eagle-import") (part "R-EU_0207/7"))
    )
    (comp (ref "R86")
      (value "0R")
      (footprint "eagle-import:0207_7")
      (libsource (lib "eagle-import") (part "R-EU_0207/7"))
    )
    (comp (ref "RS1")
      (value "J2541403-R")
      (footprint "eagle-import:6410-03")
      (libsource (lib "eagle-import") (part "22-?-0327-2031"))
    )
    (comp (ref "U3")
      (value "SN65176BD")
      (footprint "eagle-import:DIL8")
      (libsource (lib "eagle-import") (part "MAX485_DIP"))
    )
    (comp (ref "X1")
      (value "DB9 femmina")
      (footprint "eagle-import:F09HP")
      (libsource (lib "eagle-import") (part "F09HP"))
    )
    (comp (ref "XB1")
      (value "MAXSTREAM_XBEE-PRO")
      (footprint "eagle-import:MAXSTREAM_XBEE-PRO")
      (libsource (lib "eagle-import") (part "MAXSTREAM_XBEE-PRO"))
    )
    (comp (ref "C12")
      (value "100nF p5.08")
      (footprint "eagle-import:C050-024X044")
      (libsource (lib "eagle-import") (part "C-EU050-024X044"))
    )
    (comp (ref "C13")
      (value "100nF p5.08")
      (footprint "eagle-import:C050-024X044")
      (libsource (lib "eagle-import") (part "C-EU050-024X044"))
    )
    (comp (ref "C14")
      (value "100nF p5.08")
      (footprint "eagle-import:C050-024X044")
      (libsource (lib "eagle-import") (part "C-EU050-024X044"))
    )
    (comp (ref "C15")
      (value "100nF p5.08")
      (footprint "eagle-import:C050-024X044")
      (libsource (lib "eagle-import") (part "C-EU050-024X044"))
    )
    (comp (ref "C16")
      (value "100nF p5.08")
      (footprint "eagle-import:C050-024X044")
      (libsource (lib "eagle-import") (part "C-EU050-024X044"))
    )
    (comp (ref "C17")
      (value "100nF p5.08")
      (footprint "eagle-import:C050-024X044")
      (libsource (lib "eagle-import") (part "C-EU050-024X044"))
    )
    (comp (ref "C18")
      (value "100nF p5.08")
      (footprint "eagle-import:C050-024X044")
      (libsource (lib "eagle-import") (part "C-EU050-024X044"))
    )
    (comp (ref "C19")
      (value "100nF p5.08")
      (footprint "eagle-import:C050-024X044")
      (libsource (lib "eagle-import") (part "C-EU050-024X044"))
    )
    (comp (ref "C20")
      (value "100nF p5.08")
      (footprint "eagle-import:C050-024X044")
      (libsource (lib "eagle-import") (part "C-EU050-024X044"))
    )
    (comp (ref "C21")
      (value "100nF p5.08")
      (footprint "eagle-import:C050-024X044")
      (libsource (lib "eagle-import") (part "C-EU050-024X044"))
    )
    (comp (ref "C22")
      (value "100nF p5.08")
      (footprint "eagle-import:C050-024X044")
      (libsource (lib "eagle-import") (part "C-EU050-024X044"))
    )
    (comp (ref "C23")
      (value "100nF p5.08")
      (footprint "eagle-import:C050-024X044")
      (libsource (lib "eagle-import") (part "C-EU050-024X044"))
    )
    (comp (ref "C24")
      (value "100nF p5.08")
      (footprint "eagle-import:C050-024X044")
      (libsource (lib "eagle-import") (part "C-EU050-024X044"))
    )
    (comp (ref "C25")
      (value "100nF p5.08")
      (footprint "eagle-import:C050-024X044")
      (libsource (lib "eagle-import") (part "C-EU050-024X044"))
    )
    (comp (ref "C26")
      (value "100nF p5.08")
      (footprint "eagle-import:C050-024X044")
      (libsource (lib "eagle-import") (part "C-EU050-024X044"))
    )
    (comp (ref "C27")
      (value "100nF p5.08")
      (footprint "eagle-import:C050-024X044")
      (libsource (lib "eagle-import") (part "C-EU050-024X044"))
    )
    (comp (ref "C28")
      (value "100nF p5.08")
      (footprint "eagle-import:C050-024X044")
      (libsource (lib "eagle-import") (part "C-EU050-024X044"))
    )
    (comp (ref "C29")
      (value "100nF p5.08")
      (footprint "eagle-import:C050-024X044")
      (libsource (lib "eagle-import") (part "C-EU050-024X044"))
    )
    (comp (ref "C30")
      (value "100uF 25V p2.54")
      (footprint "eagle-import:E2,5-6")
      (libsource (lib "eagle-import") (part "CPOL-EUE2.5-6"))
    )
    (comp (ref "C31")
      (value "100uF 25V p2.54")
      (footprint "eagle-import:E2,5-6")
      (libsource (lib "eagle-import") (part "CPOL-EUE2.5-6"))
    )
    (comp (ref "CN2")
      (value "10.8060.0008")
      (footprint "eagle-import:300-021-13_2P_5VE")
      (libsource (lib "eagle-import") (part "10.8060.0008"))
    )
    (comp (ref "IC1")
      (value "74HC4067DB")
      (footprint "eagle-import:SO24W")
      (libsource (lib "eagle-import") (part "4067D"))
    )
    (comp (ref "IC2")
      (value "74HC4067DB")
      (footprint "eagle-import:SO24W")
      (libsource (lib "eagle-import") (part "4067D"))
    )
    (comp (ref "JP3")
      (value "JP1E")
      (footprint "eagle-import:JP1")
      (libsource (lib "eagle-import") (part "JP1E"))
    )
    (comp (ref "L1")
      (value "L-EU2200-12.7")
      (footprint "eagle-import:2200-12.7")
      (libsource (lib "eagle-import") (part "L-EU2200-12.7"))
    )
    (comp (ref "SN1")
      (value "22-27-2041-04")
      (footprint "eagle-import:6410-04")
      (libsource (lib "eagle-import") (part "22-?-0427-2041"))
    )
    (comp (ref "SN2")
      (value "22-27-2041-04")
      (footprint "eagle-import:6410-04")
      (libsource (lib "eagle-import") (part "22-?-0427-2041"))
    )
    (comp (ref "SN3")
      (value "22-27-2041-04")
      (footprint "eagle-import:6410-04")
      (libsource (lib "eagle-import") (part "22-?-0427-2041"))
    )
    (comp (ref "SN4")
      (value "22-27-2041-04")
      (footprint "eagle-import:6410-04")
      (libsource (lib "eagle-import") (part "22-?-0427-2041"))
    )
    (comp (ref "SN5")
      (value "22-27-2041-04")
      (footprint "eagle-import:6410-04")
      (libsource (lib "eagle-import") (part "22-?-0427-2041"))
    )
    (comp (ref "SN6")
      (value "22-27-2041-04")
      (footprint "eagle-import:6410-04")
      (libsource (lib "eagle-import") (part "22-?-0427-2041"))
    )
    (comp (ref "SN7")
      (value "22-27-2041-04")
      (footprint "eagle-import:6410-04")
      (libsource (lib "eagle-import") (part "22-?-0427-2041"))
    )
    (comp (ref "SN8")
      (value "22-27-2041-04")
      (footprint "eagle-import:6410-04")
      (libsource (lib "eagle-import") (part "22-?-0427-2041"))
    )
    (comp (ref "SN9")
      (value "22-27-2041-04")
      (footprint "eagle-import:6410-04")
      (libsource (lib "eagle-import") (part "22-?-0427-2041"))
    )
    (comp (ref "SN10")
      (value "22-27-2041-04")
      (footprint "eagle-import:6410-04")
      (libsource (lib "eagle-import") (part "22-?-0427-2041"))
    )
    (comp (ref "SN11")
      (value "22-27-2041-04")
      (footprint "eagle-import:6410-04")
      (libsource (lib "eagle-import") (part "22-?-0427-2041"))
    )
    (comp (ref "SN12")
      (value "22-27-2041-04")
      (footprint "eagle-import:6410-04")
      (libsource (lib "eagle-import") (part "22-?-0427-2041"))
    )
    (comp (ref "SN13")
      (value "22-27-2041-04")
      (footprint "eagle-import:6410-04")
      (libsource (lib "eagle-import") (part "22-?-0427-2041"))
    )
    (comp (ref "SN14")
      (value "22-27-2041-04")
      (footprint "eagle-import:6410-04")
      (libsource (lib "eagle-import") (part "22-?-0427-2041"))
    )
    (comp (ref "SN15")
      (value "22-27-2041-04")
      (footprint "eagle-import:6410-04")
      (libsource (lib "eagle-import") (part "22-?-0427-2041"))
    )
    (comp (ref "SN16")
      (value "22-27-2041-04")
      (footprint "eagle-import:6410-04")
      (libsource (lib "eagle-import") (part "22-?-0427-2041"))
    )
    (comp (ref "CN3")
      (value "SATA-7")
      (footprint "eagle-import:SATA-5607-5102-SH")
      (libsource (lib "eagle-import") (part "SATA-7"))
    )
    (comp (ref "CN4")
      (value "SATA-7")
      (footprint "eagle-import:SATA-5607-5102-SH")
      (libsource (lib "eagle-import") (part "SATA-7"))
    )
    (comp (ref "ENC_1")
      (value "J2541406-R")
      (footprint "eagle-import:6410-06")
      (libsource (lib "eagle-import") (part "22-?-0627-2061"))
    )
    (comp (ref "ENC_2")
      (value "J2541406-R")
      (footprint "eagle-import:6410-06")
      (libsource (lib "eagle-import") (part "22-?-0627-2061"))
    )
    (comp (ref "JP4")
      (value "STREP3x2VERT")
      (footprint "eagle-import:JP3Q")
      (libsource (lib "eagle-import") (part "JP3Q"))
    )
    (comp (ref "JP5")
      (value "STREP3x2VERT")
      (footprint "eagle-import:JP3Q")
      (libsource (lib "eagle-import") (part "JP3Q"))
    )
    (comp (ref "JP6")
      (value "STREP3x2VERT")
      (footprint "eagle-import:JP3Q")
      (libsource (lib "eagle-import") (part "JP3Q"))
    )
    (comp (ref "JP7")
      (value "STREP3x2VERT")
      (footprint "eagle-import:JP3Q")
      (libsource (lib "eagle-import") (part "JP3Q"))
    )
    (comp (ref "MOT_1")
      (value "J2541406-R")
      (footprint "eagle-import:6410-06")
      (libsource (lib "eagle-import") (part "22-?-0627-2061"))
    )
    (comp (ref "MOT_2")
      (value "J2541406-R")
      (footprint "eagle-import:6410-06")
      (libsource (lib "eagle-import") (part "22-?-0627-2061"))
    )
    (comp (ref "POW")
      (value "J2541406-R")
      (footprint "eagle-import:6410-06")
      (libsource (lib "eagle-import") (part "22-?-0627-2061"))
    )
    (comp (ref "R57")
      (value "10K")
      (footprint "eagle-import:0207_7")
      (libsource (lib "eagle-import") (part "R-EU_0207/7"))
    )
    (comp (ref "R58")
      (value "10K")
      (footprint "eagle-import:0207_7")
      (libsource (lib "eagle-import") (part "R-EU_0207/7"))
    )
    (comp (ref "R59")
      (value "10K")
      (footprint "eagle-import:0207_7")
      (libsource (lib "eagle-import") (part "R-EU_0207/7"))
    )
    (comp (ref "R60")
      (value "22K")
      (footprint "eagle-import:0207_7")
      (libsource (lib "eagle-import") (part "R-EU_0207/7"))
    )
    (comp (ref "R61")
      (value "22K")
      (footprint "eagle-import:0207_7")
      (libsource (lib "eagle-import") (part "R-EU_0207/7"))
    )
    (comp (ref "R62")
      (value "22K")
      (footprint "eagle-import:0207_7")
      (libsource (lib "eagle-import") (part "R-EU_0207/7"))
    )
    (comp (ref "R63")
      (value "4K7")
      (footprint "eagle-import:0207_7")
      (libsource (lib "eagle-import") (part "R-EU_0207/7"))
    )
    (comp (ref "R64")
      (value "4K7")
      (footprint "eagle-import:0207_7")
      (libsource (lib "eagle-import") (part "R-EU_0207/7"))
    )
    (comp (ref "R65")
      (value "4K7")
      (footprint "eagle-import:0207_7")
      (libsource (lib "eagle-import") (part "R-EU_0207/7"))
    )
    (comp (ref "R66")
      (value "10K")
      (footprint "eagle-import:0207_7")
      (libsource (lib "eagle-import") (part "R-EU_0207/7"))
    )
    (comp (ref "R67")
      (value "10K")
      (footprint "eagle-import:0207_7")
      (libsource (lib "eagle-import") (part "R-EU_0207/7"))
    )
    (comp (ref "R68")
      (value "10K")
      (footprint "eagle-import:0207_7")
      (libsource (lib "eagle-import") (part "R-EU_0207/7"))
    )
    (comp (ref "R69")
      (value "22K")
      (footprint "eagle-import:0207_7")
      (libsource (lib "eagle-import") (part "R-EU_0207/7"))
    )
    (comp (ref "R70")
      (value "22K")
      (footprint "eagle-import:0207_7")
      (libsource (lib "eagle-import") (part "R-EU_0207/7"))
    )
    (comp (ref "R71")
      (value "22K")
      (footprint "eagle-import:0207_7")
      (libsource (lib "eagle-import") (part "R-EU_0207/7"))
    )
    (comp (ref "R72")
      (value "4K7")
      (footprint "eagle-import:0207_7")
      (libsource (lib "eagle-import") (part "R-EU_0207/7"))
    )
    (comp (ref "R73")
      (value "4K7")
      (footprint "eagle-import:0207_7")
      (libsource (lib "eagle-import") (part "R-EU_0207/7"))
    )
    (comp (ref "R74")
      (value "4K7")
      (footprint "eagle-import:0207_7")
      (libsource (lib "eagle-import") (part "R-EU_0207/7"))
    )
  )
  (nets
    (net (code "1") (name "+3V3") (class "Default")
      (node (ref "C2") (pin "1") (pinfunction "1_1") (pintype "passive"))
      (node (ref "C36") (pin "2") (pinfunction "2_2") (pintype "passive"))
      (node (ref "C37") (pin "-") (pinfunction "-_-") (pintype "passive"))
      (node (ref "C40") (pin "+") (pinfunction "+_+") (pintype "passive"))
      (node (ref "C41") (pin "1") (pinfunction "1_1") (pintype "passive"))
      (node (ref "C6") (pin "+") (pinfunction "+_+") (pintype "passive"))
      (node (ref "C7") (pin "1") (pinfunction "1_1") (pintype "passive"))
      (node (ref "C8") (pin "1") (pinfunction "1_1") (pintype "passive"))
      (node (ref "DIS1") (pin "3") (pinfunction "VDD_3") (pintype "bidirectional"))
      (node (ref "DIS1") (pin "4") (pinfunction "VDD1_4") (pintype "bidirectional"))
      (node (ref "DIS1") (pin "55") (pinfunction "VDD2_55") (pintype "bidirectional"))
      (node (ref "DIS1") (pin "56") (pinfunction "VDD3_56") (pintype "bidirectional"))
      (node (ref "DIS1") (pin "72") (pinfunction "VDD4_72") (pintype "bidirectional"))
      (node (ref "IC4") (pin "16") (pinfunction "VCC_16") (pintype "power_in"))
      (node (ref "POW") (pin "2") (pinfunction "S_2") (pintype "passive"))
      (node (ref "R2") (pin "1") (pinfunction "1_1") (pintype "passive"))
      (node (ref "R76") (pin "1") (pinfunction "1_1") (pintype "passive"))
      (node (ref "R78") (pin "1") (pinfunction "1_1") (pintype "passive"))
      (node (ref "R87") (pin "1") (pinfunction "1_1") (pintype "passive"))
      (node (ref "R88") (pin "1") (pinfunction "1_1") (pintype "passive"))
      (node (ref "U2") (pin "2") (pinfunction "OUT_2") (pintype "passive"))
      (node (ref "XB1") (pin "1") (pinfunction "VCC_1") (pintype "power_in"))
    )
    (net (code "2") (name "+5V") (class "Default")
      (node (ref "C3") (pin "1") (pinfunction "1_1") (pintype "passive"))
      (node (ref "C39") (pin "1") (pinfunction "1_1") (pintype "passive"))
      (node (ref "C4") (pin "+") (pinfunction "+_+") (pintype "passive"))
      (node (ref "C9") (pin "1") (pinfunction "1_1") (pintype "passive"))
      (node (ref "DIS1") (pin "53") (pinfunction "5V_53") (pintype "bidirectional"))
      (node (ref "DIS1") (pin "54") (pinfunction "5V2_54") (pintype "bidirectional"))
      (node (ref "ENC_1") (pin "6") (pinfunction "S_6") (pintype "passive"))
      (node (ref "ENC_2") (pin "6") (pinfunction "S_6") (pintype "passive"))
      (node (ref "JP1") (pin "2") (pinfunction "2_2") (pintype "passive"))
      (node (ref "JP3") (pin "1") (pinfunction "1_1") (pintype "passive"))
      (node (ref "JP4") (pin "2") (pinfunction "2_2") (pintype "passive"))
      (node (ref "JP4") (pin "4") (pinfunction "4_4") (pintype "passive"))
      (node (ref "JP4") (pin "6") (pinfunction "6_6") (pintype "passive"))
      (node (ref "JP6") (pin "2") (pinfunction "2_2") (pintype "passive"))
      (node (ref "JP6") (pin "4") (pinfunction "4_4") (pintype "passive"))
      (node (ref "JP6") (pin "6") (pinfunction "6_6") (pintype "passive"))
      (node (ref "MOT_1") (pin "1") (pinfunction "S_1") (pintype "passive"))
      (node (ref "MOT_2") (pin "1") (pinfunction "S_1") (pintype "passive"))
      (node (ref "POW") (pin "4") (pinfunction "S_4") (pintype "passive"))
      (node (ref "R1") (pin "1") (pinfunction "1_1") (pintype "passive"))
      (node (ref "R75") (pin "1") (pinfunction "1_1") (pintype "passive"))
      (node (ref "R77") (pin "1") (pinfunction "1_1") (pintype "passive"))
      (node (ref "R85") (pin "1") (pinfunction "1_1") (pintype "passive"))
      (node (ref "U1") (pin "OUT") (pinfunction "OUT_OUT") (pintype "passive"))
      (node (ref "U2") (pin "3") (pinfunction "IN_3") (pintype "input"))
      (node (ref "U3") (pin "8") (pinfunction "VCC_8") (pintype "bidirectional"))
    )
    (net (code "3") (name "+5V{slash}1") (class "Default")
      (node (ref "C12") (pin "1") (pinfunction "1_1") (pintype "passive"))
      (node (ref "C13") (pin "1") (pinfunction "1_1") (pintype "passive"))
      (node (ref "C14") (pin "1") (pinfunction "1_1") (pintype "passive"))
      (node (ref "C15") (pin "1") (pinfunction "1_1") (pintype "passive"))
      (node (ref "C16") (pin "1") (pinfunction "1_1") (pintype "passive"))
      (node (ref "C17") (pin "1") (pinfunction "1_1") (pintype "passive"))
      (node (ref "C18") (pin "1") (pinfunction "1_1") (pintype "passive"))
      (node (ref "C19") (pin "1") (pinfunction "1_1") (pintype "passive"))
      (node (ref "C20") (pin "1") (pinfunction "1_1") (pintype "passive"))
      (node (ref "C21") (pin "1") (pinfunction "1_1") (pintype "passive"))
      (node (ref "C22") (pin "1") (pinfunction "1_1") (pintype "passive"))
      (node (ref "C23") (pin "1") (pinfunction "1_1") (pintype "passive"))
      (node (ref "C24") (pin "1") (pinfunction "1_1") (pintype "passive"))
      (node (ref "C25") (pin "1") (pinfunction "1_1") (pintype "passive"))
      (node (ref "C26") (pin "1") (pinfunction "1_1") (pintype "passive"))
      (node (ref "C27") (pin "1") (pinfunction "1_1") (pintype "passive"))
      (node (ref "C28") (pin "1") (pinfunction "1_1") (pintype "passive"))
      (node (ref "C29") (pin "1") (pinfunction "1_1") (pintype "passive"))
      (node (ref "C31") (pin "+") (pinfunction "+_+") (pintype "passive"))
      (node (ref "IC1") (pin "24") (pinfunction "VDD_24") (pintype "power_in"))
      (node (ref "IC1B") (pin "24") (pinfunction "VDD_24") (pintype "power_in"))
      (node (ref "IC2") (pin "24") (pinfunction "VDD_24") (pintype "power_in"))
      (node (ref "IC2B") (pin "24") (pinfunction "VDD_24") (pintype "power_in"))
      (node (ref "IC3") (pin "10") (pinfunction "CD+_10") (pintype "passive"))
      (node (ref "L1") (pin "2") (pinfunction "2_2") (pintype "passive"))
      (node (ref "Q1") (pin "E") (pinfunction "E_E") (pintype "passive"))
      (node (ref "Q2") (pin "E") (pinfunction "E_E") (pintype "passive"))
      (node (ref "Q3") (pin "E") (pinfunction "E_E") (pintype "passive"))
      (node (ref "Q4") (pin "E") (pinfunction "E_E") (pintype "passive"))
      (node (ref "Q5") (pin "E") (pinfunction "E_E") (pintype "passive"))
      (node (ref "Q6") (pin "E") (pinfunction "E_E") (pintype "passive"))
      (node (ref "SN1") (pin "1") (pinfunction "S_1") (pintype "passive"))
      (node (ref "SN10") (pin "1") (pinfunction "S_1") (pintype "passive"))
      (node (ref "SN11") (pin "1") (pinfunction "S_1") (pintype "passive"))
      (node (ref "SN12") (pin "1") (pinfunction "S_1") (pintype "passive"))
      (node (ref "SN13") (pin "1") (pinfunction "S_1") (pintype "passive"))
      (node (ref "SN14") (pin "1") (pinfunction "S_1") (pintype "passive"))
      (node (ref "SN15") (pin "1") (pinfunction "S_1") (pintype "passive"))
      (node (ref "SN16") (pin "1") (pinfunction "S_1") (pintype "passive"))
      (node (ref "SN2") (pin "1") (pinfunction "S_1") (pintype "passive"))
      (node (ref "SN3") (pin "1") (pinfunction "S_1") (pintype "passive"))
      (node (ref "SN4") (pin "1") (pinfunction "S_1") (pintype "passive"))
      (node (ref "SN5") (pin "1") (pinfunction "S_1") (pintype "passive"))
      (node (ref "SN6") (pin "1") (pinfunction "S_1") (pintype "passive"))
      (node (ref "SN7") (pin "1") (pinfunction "S_1") (pintype "passive"))
      (node (ref "SN8") (pin "1") (pinfunction "S_1") (pintype "passive"))
      (node (ref "SN9") (pin "1") (pinfunction "S_1") (pintype "passive"))
    )
    (net (code "4") (name "+24V") (class "Default")
      (node (ref "POW") (pin "6") (pinfunction "S_6") (pintype "passive"))
    )
    (net (code "5") (name "A") (class "Default")
      (node (ref "JP11") (pin "6") (pinfunction "6_6") (pintype "passive"))
      (node (ref "R80") (pin "2") (pinfunction "2_2") (pintype "passive"))
      (node (ref "R83") (pin "1") (pinfunction "1_1") (pintype "passive"))
      (node (ref "RS1") (pin "3") (pinfunction "S_3") (pintype "passive"))
      (node (ref "U3") (pin "6") (pinfunction "A_6") (pintype "passive"))
    )
    (net (code "6") (name "A1") (class "Default")
      (node (ref "ENC_2") (pin "4") (pinfunction "S_4") (pintype "passive"))
      (node (ref "R66") (pin "1") (pinfunction "1_1") (pintype "passive"))
      (node (ref "R69") (pin "2") (pinfunction "2_2") (pintype "passive"))
    )
    (net (code "7") (name "A2") (class "Default")
      (node (ref "ENC_1") (pin "4") (pinfunction "S_4") (pintype "passive"))
      (node (ref "R57") (pin "1") (pinfunction "1_1") (pintype "passive"))
      (node (ref "R60") (pin "2") (pinfunction "2_2") (pintype "passive"))
    )
    (net (code "8") (name "B") (class "Default")
      (node (ref "JP11") (pin "2") (pinfunction "2_2") (pintype "passive"))
      (node (ref "JP11") (pin "4") (pinfunction "4_4") (pintype "passive"))
      (node (ref "R86") (pin "1") (pinfunction "1_1") (pintype "passive"))
      (node (ref "RS1") (pin "1") (pinfunction "S_1") (pintype "passive"))
      (node (ref "U3") (pin "7") (pinfunction "B_7") (pintype "passive"))
    )
    (net (code "9") (name "B1") (class "Default")
      (node (ref "ENC_2") (pin "3") (pinfunction "S_3") (pintype "passive"))
      (node (ref "R67") (pin "1") (pinfunction "1_1") (pintype "passive"))
      (node (ref "R70") (pin "2") (pinfunction "2_2") (pintype "passive"))
    )
    (net (code "10") (name "B2") (class "Default")
      (node (ref "ENC_1") (pin "3") (pinfunction "S_3") (pintype "passive"))
      (node (ref "R58") (pin "1") (pinfunction "1_1") (pintype "passive"))
      (node (ref "R61") (pin "2") (pinfunction "2_2") (pintype "passive"))
    )
    (net (code "11") (name "BMP085_CLR") (class "Default")
      (node (ref "DIS1") (pin "32") (pinfunction "PE14_32") (pintype "bidirectional"))
      (node (ref "JP2") (pin "3") (pinfunction "3_3") (pintype "passive"))
    )
    (net (code "12") (name "BMP085_EOC") (class "Default")
      (node (ref "DIS1") (pin "33") (pinfunction "PE15_33") (pintype "bidirectional"))
      (node (ref "JP2") (pin "2") (pinfunction "2_2") (pintype "passive"))
    )
    (net (code "13") (name "BMP085_SCL") (class "Default")
      (node (ref "DIS1") (pin "34") (pinfunction "PB10_34") (pintype "bidirectional"))
      (node (ref "JP2") (pin "4") (pinfunction "4_4") (pintype "passive"))
    )
    (net (code "14") (name "BMP085_SDA") (class "Default")
      (node (ref "DIS1") (pin "35") (pinfunction "PB11_35") (pintype "bidirectional"))
      (node (ref "JP2") (pin "5") (pinfunction "5_5") (pintype "passive"))
    )
    (net (code "15") (name "COM1-RX") (class "Default")
      (node (ref "JP12") (pin "2") (pinfunction "2_2") (pintype "passive"))
      (node (ref "XB1") (pin "2") (pinfunction "DOUT_2") (pintype "output"))
    )
    (net (code "16") (name "COM1-TX") (class "Default")
      (node (ref "JP12") (pin "4") (pinfunction "4_4") (pintype "passive"))
      (node (ref "XB1") (pin "3") (pinfunction "DIN/~{CONFIG}_3") (pintype "input"))
    )
    (net (code "17") (name "ECHO_MUX") (class "Default")
      (node (ref "DIS1") (pin "38") (pinfunction "PB14_38") (pintype "bidirectional"))
      (node (ref "IC2") (pin "1") (pinfunction "X_1") (pintype "output"))
      (node (ref "IC2B") (pin "1") (pinfunction "X_1") (pintype "output"))
    )
    (net (code "18") (name "ECHO_U1") (class "Default")
      (node (ref "IC2") (pin "9") (pinfunction "X0_9") (pintype "input"))
      (node (ref "IC2B") (pin "9") (pinfunction "X0_9") (pintype "input"))
      (node (ref "SN1") (pin "3") (pinfunction "S_3") (pintype "passive"))
    )
    (net (code "19") (name "ECHO_U2") (class "Default")
      (node (ref "IC2") (pin "8") (pinfunction "X1_8") (pintype "input"))
      (node (ref "IC2B") (pin "8") (pinfunction "X1_8") (pintype "input"))
      (node (ref "SN2") (pin "3") (pinfunction "S_3") (pintype "passive"))
    )
    (net (code "20") (name "ECHO_U3") (class "Default")
      (node (ref "IC2") (pin "7") (pinfunction "X2_7") (pintype "input"))
      (node (ref "IC2B") (pin "7") (pinfunction "X2_7") (pintype "input"))
      (node (ref "SN3") (pin "3") (pinfunction "S_3") (pintype "passive"))
    )
    (net (code "21") (name "ECHO_U4") (class "Default")
      (node (ref "IC2") (pin "6") (pinfunction "X3_6") (pintype "input"))
      (node (ref "IC2B") (pin "6") (pinfunction "X3_6") (pintype "input"))
      (node (ref "SN4") (pin "3") (pinfunction "S_3") (pintype "passive"))
    )
    (net (code "22") (name "ECHO_U5") (class "Default")
      (node (ref "IC2") (pin "5") (pinfunction "X4_5") (pintype "input"))
      (node (ref "IC2B") (pin "5") (pinfunction "X4_5") (pintype "input"))
      (node (ref "SN5") (pin "3") (pinfunction "S_3") (pintype "passive"))
    )
    (net (code "23") (name "ECHO_U6") (class "Default")
      (node (ref "IC2") (pin "4") (pinfunction "X5_4") (pintype "input"))
      (node (ref "IC2B") (pin "4") (pinfunction "X5_4") (pintype "input"))
      (node (ref "SN6") (pin "3") (pinfunction "S_3") (pintype "passive"))
    )
    (net (code "24") (name "ECHO_U7") (class "Default")
      (node (ref "IC2") (pin "3") (pinfunction "X6_3") (pintype "input"))
      (node (ref "IC2B") (pin "3") (pinfunction "X6_3") (pintype "input"))
      (node (ref "SN7") (pin "3") (pinfunction "S_3") (pintype "passive"))
    )
    (net (code "25") (name "ECHO_U8") (class "Default")
      (node (ref "IC2") (pin "2") (pinfunction "X7_2") (pintype "input"))
      (node (ref "IC2B") (pin "2") (pinfunction "X7_2") (pintype "input"))
      (node (ref "SN8") (pin "3") (pinfunction "S_3") (pintype "passive"))
    )
    (net (code "26") (name "ECHO_U9") (class "Default")
      (node (ref "IC2") (pin "23") (pinfunction "X8_23") (pintype "input"))
      (node (ref "IC2B") (pin "23") (pinfunction "X8_23") (pintype "input"))
      (node (ref "SN9") (pin "3") (pinfunction "S_3") (pintype "passive"))
    )
    (net (code "27") (name "ECHO_U10") (class "Default")
      (node (ref "IC2") (pin "22") (pinfunction "X9_22") (pintype "input"))
      (node (ref "IC2B") (pin "22") (pinfunction "X9_22") (pintype "input"))
      (node (ref "SN10") (pin "3") (pinfunction "S_3") (pintype "passive"))
    )
    (net (code "28") (name "ECHO_U11") (class "Default")
      (node (ref "IC2") (pin "21") (pinfunction "X10_21") (pintype "input"))
      (node (ref "IC2B") (pin "21") (pinfunction "X10_21") (pintype "input"))
      (node (ref "SN11") (pin "3") (pinfunction "S_3") (pintype "passive"))
    )
    (net (code "29") (name "ECHO_U12") (class "Default")
      (node (ref "IC2") (pin "20") (pinfunction "X11_20") (pintype "input"))
      (node (ref "IC2B") (pin "20") (pinfunction "X11_20") (pintype "input"))
      (node (ref "SN12") (pin "3") (pinfunction "S_3") (pintype "passive"))
    )
    (net (code "30") (name "ECHO_U13") (class "Default")
      (node (ref "IC2") (pin "19") (pinfunction "X12_19") (pintype "input"))
      (node (ref "IC2B") (pin "19") (pinfunction "X12_19") (pintype "input"))
      (node (ref "SN13") (pin "3") (pinfunction "S_3") (pintype "passive"))
    )
    (net (code "31") (name "ECHO_U14") (class "Default")
      (node (ref "IC2") (pin "18") (pinfunction "X13_18") (pintype "input"))
      (node (ref "IC2B") (pin "18") (pinfunction "X13_18") (pintype "input"))
      (node (ref "SN14") (pin "3") (pinfunction "S_3") (pintype "passive"))
    )
    (net (code "32") (name "ECHO_U15") (class "Default")
      (node (ref "IC2") (pin "17") (pinfunction "X14_17") (pintype "input"))
      (node (ref "IC2B") (pin "17") (pinfunction "X14_17") (pintype "input"))
      (node (ref "SN15") (pin "3") (pinfunction "S_3") (pintype "passive"))
    )
    (net (code "33") (name "ECHO_U16") (class "Default")
      (node (ref "IC2") (pin "16") (pinfunction "X15_16") (pintype "input"))
      (node (ref "IC2B") (pin "16") (pinfunction "X15_16") (pintype "input"))
      (node (ref "SN16") (pin "3") (pinfunction "S_3") (pintype "passive"))
    )
    (net (code "34") (name "ENC1_A") (class "Default")
      (node (ref "DIS1") (pin "15") (pinfunction "PA5_15") (pintype "bidirectional"))
      (node (ref "R60") (pin "1") (pinfunction "1_1") (pintype "passive"))
      (node (ref "R63") (pin "2") (pinfunction "2_2") (pintype "passive"))
    )
    (net (code "35") (name "ENC1_B") (class "Default")
      (node (ref "DIS1") (pin "11") (pinfunction "PA1_11") (pintype "bidirectional"))
      (node (ref "R61") (pin "1") (pinfunction "1_1") (pintype "passive"))
      (node (ref "R64") (pin "2") (pinfunction "2_2") (pintype "passive"))
    )
    (net (code "36") (name "ENC1_IDX") (class "Default")
      (node (ref "DIS1") (pin "20") (pinfunction "PC4_20") (pintype "bidirectional"))
      (node (ref "R62") (pin "1") (pinfunction "1_1") (pintype "passive"))
      (node (ref "R65") (pin "2") (pinfunction "2_2") (pintype "passive"))
    )
    (net (code "37") (name "ENC2_A") (class "Default")
      (node (ref "DIS1") (pin "18") (pinfunction "PA6_18") (pintype "bidirectional"))
      (node (ref "R69") (pin "1") (pinfunction "1_1") (pintype "passive"))
      (node (ref "R72") (pin "2") (pinfunction "2_2") (pintype "passive"))
    )
    (net (code "38") (name "ENC2_B") (class "Default")
      (node (ref "DIS1") (pin "17") (pinfunction "PA7_17") (pintype "bidirectional"))
      (node (ref "R70") (pin "1") (pinfunction "1_1") (pintype "passive"))
      (node (ref "R73") (pin "2") (pinfunction "2_2") (pintype "passive"))
    )
    (net (code "39") (name "ENC2_IDX") (class "Default")
      (node (ref "DIS1") (pin "16") (pinfunction "PA4_16") (pintype "bidirectional"))
      (node (ref "R71") (pin "1") (pinfunction "1_1") (pintype "passive"))
      (node (ref "R74") (pin "2") (pinfunction "2_2") (pintype "passive"))
    )
    (net (code "40") (name "F4_UART1_DIR") (class "Default")
      (node (ref "DIS1") (pin "76") (pinfunction "PB5_76") (pintype "bidirectional"))
      (node (ref "J1") (pin "2") (pinfunction "S_2") (pintype "passive"))
      (node (ref "JP9") (pin "4") (pinfunction "4_4") (pintype "passive"))
    )
    (net (code "41") (name "F4_UART1_RX") (class "Default")
      (node (ref "DIS1") (pin "74") (pinfunction "PB7_74") (pintype "bidirectional"))
      (node (ref "J1") (pin "3") (pinfunction "S_3") (pintype "passive"))
      (node (ref "JP9") (pin "6") (pinfunction "6_6") (pintype "passive"))
    )
    (net (code "42") (name "F4_UART1_TX") (class "Default")
      (node (ref "DIS1") (pin "73") (pinfunction "PB6_73") (pintype "bidirectional"))
      (node (ref "J1") (pin "4") (pinfunction "S_4") (pintype "passive"))
      (node (ref "JP9") (pin "2") (pinfunction "2_2") (pintype "passive"))
    )
    (net (code "43") (name "F4_UART2_DIR") (class "Default")
      (node (ref "DIS1") (pin "12") (pinfunction "PA0_12") (pintype "bidirectional"))
      (node (ref "J2") (pin "2") (pinfunction "S_2") (pintype "passive"))
    )
    (net (code "44") (name "F4_UART2_RX") (class "Default")
      (node (ref "DIS1") (pin "13") (pinfunction "PA3_13") (pintype "bidirectional"))
      (node (ref "J2") (pin "3") (pinfunction "S_3") (pintype "passive"))
      (node (ref "JP12") (pin "1") (pinfunction "1_1") (pintype "passive"))
      (node (ref "JP8") (pin "2") (pinfunction "2_2") (pintype "passive"))
    )
    (net (code "45") (name "F4_UART2_TX") (class "Default")
      (node (ref "DIS1") (pin "14") (pinfunction "PA2_14") (pintype "bidirectional"))
      (node (ref "J2") (pin "4") (pinfunction "S_4") (pintype "passive"))
      (node (ref "JP12") (pin "3") (pinfunction "3_3") (pintype "passive"))
      (node (ref "JP8") (pin "4") (pinfunction "4_4") (pintype "passive"))
    )
    (net (code "46") (name "GND") (class "Default")
      (node (ref "C1") (pin "-") (pinfunction "-_-") (pintype "passive"))
      (node (ref "C12") (pin "2") (pinfunction "2_2") (pintype "passive"))
      (node (ref "C13") (pin "2") (pinfunction "2_2") (pintype "passive"))
      (node (ref "C14") (pin "2") (pinfunction "2_2") (pintype "passive"))
      (node (ref "C15") (pin "2") (pinfunction "2_2") (pintype "passive"))
      (node (ref "C16") (pin "2") (pinfunction "2_2") (pintype "passive"))
      (node (ref "C17") (pin "2") (pinfunction "2_2") (pintype "passive"))
      (node (ref "C18") (pin "2") (pinfunction "2_2") (pintype "passive"))
      (node (ref "C19") (pin "2") (pinfunction "2_2") (pintype "passive"))
      (node (ref "C2") (pin "2") (pinfunction "2_2") (pintype "passive"))
      (node (ref "C20") (pin "2") (pinfunction "2_2") (pintype "passive"))
      (node (ref "C21") (pin "2") (pinfunction "2_2") (pintype "passive"))
      (node (ref "C22") (pin "2") (pinfunction "2_2") (pintype "passive"))
      (node (ref "C23") (pin "2") (pinfunction "2_2") (pintype "passive"))
      (node (ref "C24") (pin "2") (pinfunction "2_2") (pintype "passive"))
      (node (ref "C25") (pin "2") (pinfunction "2_2") (pintype "passive"))
      (node (ref "C26") (pin "2") (pinfunction "2_2") (pintype "passive"))
      (node (ref "C27") (pin "2") (pinfunction "2_2") (pintype "passive"))
      (node (ref "C28") (pin "2") (pinfunction "2_2") (pintype "passive"))
      (node (ref "C29") (pin "2") (pinfunction "2_2") (pintype "passive"))
      (node (ref "C3") (pin "2") (pinfunction "2_2") (pintype "passive"))
      (node (ref "C30") (pin "-") (pinfunction "-_-") (pintype "passive"))
      (node (ref "C31") (pin "-") (pinfunction "-_-") (pintype "passive"))
      (node (ref "C32") (pin "2") (pinfunction "2_2") (pintype "passive"))
      (node (ref "C33") (pin "2") (pinfunction "2_2") (pintype "passive"))
      (node (ref "C36") (pin "1") (pinfunction "1_1") (pintype "passive"))
      (node (ref "C38") (pin "+") (pinfunction "+_+") (pintype "passive"))
      (node (ref "C39") (pin "2") (pinfunction "2_2") (pintype "passive"))
      (node (ref "C4") (pin "-") (pinfunction "-_-") (pintype "passive"))
      (node (ref "C40") (pin "-") (pinfunction "-_-") (pintype "passive"))
      (node (ref "C41") (pin "2") (pinfunction "2_2") (pintype "passive"))
      (node (ref "C6") (pin "-") (pinfunction "-_-") (pintype "passive"))
      (node (ref "C7") (pin "2") (pinfunction "2_2") (pintype "passive"))
      (node (ref "C8") (pin "2") (pinfunction "2_2") (pintype "passive"))
      (node (ref "C9") (pin "2") (pinfunction "2_2") (pintype "passive"))
      (node (ref "CN1") (pin "1") (pinfunction "S_1") (pintype "passive"))
      (node (ref "CN2") (pin "1") (pinfunction "S_1") (pintype "passive"))
      (node (ref "CN3") (pin "1") (pinfunction "GND_1") (pintype "bidirectional"))
      (node (ref "CN3") (pin "4") (pinfunction "GND_4") (pintype "bidirectional"))
      (node (ref "CN3") (pin "7") (pinfunction "GND_7") (pintype "bidirectional"))
      (node (ref "CN3") (pin "H1") (pinfunction "H1_H1") (pintype "bidirectional"))
      (node (ref "CN3") (pin "H2") (pinfunction "H2_H2") (pintype "bidirectional"))
      (node (ref "CN4") (pin "1") (pinfunction "GND_1") (pintype "bidirectional"))
      (node (ref "CN4") (pin "4") (pinfunction "GND_4") (pintype "bidirectional"))
      (node (ref "CN4") (pin "7") (pinfunction "GND_7") (pintype "bidirectional"))
      (node (ref "CN4") (pin "H1") (pinfunction "H1_H1") (pintype "bidirectional"))
      (node (ref "CN4") (pin "H2") (pinfunction "H2_H2") (pintype "bidirectional"))
      (node (ref "DIS1") (pin "1") (pinfunction "GND_1") (pintype "bidirectional"))
      (node (ref "DIS1") (pin "100") (pinfunction "GND9_100") (pintype "bidirectional"))
      (node (ref "DIS1") (pin "2") (pinfunction "GND1_2") (pintype "bidirectional"))
      (node (ref "DIS1") (pin "23") (pinfunction "GND3_23") (pintype "bidirectional"))
      (node (ref "DIS1") (pin "49") (pinfunction "GND4_49") (pintype "bidirectional"))
      (node (ref "DIS1") (pin "5") (pinfunction "GND2_5") (pintype "bidirectional"))
      (node (ref "DIS1") (pin "50") (pinfunction "GND5_50") (pintype "bidirectional"))
      (node (ref "DIS1") (pin "51") (pinfunction "GND6_51") (pintype "bidirectional"))
      (node (ref "DIS1") (pin "52") (pinfunction "GND7_52") (pintype "bidirectional"))
      (node (ref "DIS1") (pin "99") (pinfunction "GND8_99") (pintype "bidirectional"))
      (node (ref "DIS1") (pin "G1") (pinfunction "G_G1") (pintype "bidirectional"))
      (node (ref "DIS1") (pin "G2") (pinfunction "G_G2") (pintype "bidirectional"))
      (node (ref "DIS1") (pin "G3") (pinfunction "G_G3") (pintype "bidirectional"))
      (node (ref "DIS1") (pin "G4") (pinfunction "G_G4") (pintype "bidirectional"))
      (node (ref "ENC_1") (pin "1") (pinfunction "S_1") (pintype "passive"))
      (node (ref "ENC_2") (pin "1") (pinfunction "S_1") (pintype "passive"))
      (node (ref "H1") (pin "B3,3") (pinfunction "MOUNT_B3,3") (pintype "passive"))
      (node (ref "H2") (pin "B3,3") (pinfunction "MOUNT_B3,3") (pintype "passive"))
      (node (ref "H3") (pin "B3,3") (pinfunction "MOUNT_B3,3") (pintype "passive"))
      (node (ref "H4") (pin "B3,3") (pinfunction "MOUNT_B3,3") (pintype "passive"))
      (node (ref "IC1") (pin "12") (pinfunction "VSS_12") (pintype "power_in"))
      (node (ref "IC1B") (pin "12") (pinfunction "VSS_12") (pintype "power_in"))
      (node (ref "IC2") (pin "12") (pinfunction "VSS_12") (pintype "power_in"))
      (node (ref "IC2B") (pin "12") (pinfunction "VSS_12") (pintype "power_in"))
      (node (ref "IC3") (pin "9") (pinfunction "GND_9") (pintype "power_in"))
      (node (ref "IC4") (pin "15") (pinfunction "GND_15") (pintype "power_in"))
      (node (ref "J1") (pin "5") (pinfunction "S_5") (pintype "passive"))
      (node (ref "J2") (pin "5") (pinfunction "S_5") (pintype "passive"))
      (node (ref "JP2") (pin "7") (pinfunction "7_7") (pintype "passive"))
      (node (ref "JP5") (pin "1") (pinfunction "1_1") (pintype "passive"))
      (node (ref "JP5") (pin "3") (pinfunction "3_3") (pintype "passive"))
      (node (ref "JP5") (pin "5") (pinfunction "5_5") (pintype "passive"))
      (node (ref "JP7") (pin "1") (pinfunction "1_1") (pintype "passive"))
      (node (ref "JP7") (pin "3") (pinfunction "3_3") (pintype "passive"))
      (node (ref "JP7") (pin "5") (pinfunction "5_5") (pintype "passive"))
      (node (ref "LED1") (pin "K") (pinfunction "C_K") (pintype "passive"))
      (node (ref "LED2") (pin "K") (pinfunction "C_K") (pintype "passive"))
      (node (ref "MOT_1") (pin "5") (pinfunction "S_5") (pintype "passive"))
      (node (ref "MOT_2") (pin "5") (pinfunction "S_5") (pintype "passive"))
      (node (ref "P1") (pin "3") (pinfunction "S1_3") (pintype "passive"))
      (node (ref "P1") (pin "4") (pinfunction "S_4") (pintype "passive"))
      (node (ref "P2") (pin "3") (pinfunction "S1_3") (pintype "passive"))
      (node (ref "P2") (pin "4") (pinfunction "S_4") (pintype "passive"))
      (node (ref "POW") (pin "1") (pinfunction "S_1") (pintype "passive"))
      (node (ref "POW") (pin "3") (pinfunction "S_3") (pintype "passive"))
      (node (ref "POW") (pin "5") (pinfunction "S_5") (pintype "passive"))
      (node (ref "R79") (pin "1") (pinfunction "1_1") (pintype "passive"))
      (node (ref "R84") (pin "2") (pinfunction "2_2") (pintype "passive"))
      (node (ref "RS1") (pin "2") (pinfunction "S_2") (pintype "passive"))
      (node (ref "SN1") (pin "4") (pinfunction "S_4") (pintype "passive"))
      (node (ref "SN10") (pin "4") (pinfunction "S_4") (pintype "passive"))
      (node (ref "SN11") (pin "4") (pinfunction "S_4") (pintype "passive"))
      (node (ref "SN12") (pin "4") (pinfunction "S_4") (pintype "passive"))
      (node (ref "SN13") (pin "4") (pinfunction "S_4") (pintype "passive"))
      (node (ref "SN14") (pin "4") (pinfunction "S_4") (pintype "passive"))
      (node (ref "SN15") (pin "4") (pinfunction "S_4") (pintype "passive"))
      (node (ref "SN16") (pin "4") (pinfunction "S_4") (pintype "passive"))
      (node (ref "SN2") (pin "4") (pinfunction "S_4") (pintype "passive"))
      (node (ref "SN3") (pin "4") (pinfunction "S_4") (pintype "passive"))
      (node (ref "SN4") (pin "4") (pinfunction "S_4") (pintype "passive"))
      (node (ref "SN5") (pin "4") (pinfunction "S_4") (pintype "passive"))
      (node (ref "SN6") (pin "4") (pinfunction "S_4") (pintype "passive"))
      (node (ref "SN7") (pin "4") (pinfunction "S_4") (pintype "passive"))
      (node (ref "SN8") (pin "4") (pinfunction "S_4") (pintype "passive"))
      (node (ref "SN9") (pin "4") (pinfunction "S_4") (pintype "passive"))
      (node (ref "U1") (pin "GND") (pinfunction "GND_GND") (pintype "input"))
      (node (ref "U2") (pin "1") (pinfunction "ADJ_1") (pintype "input"))
      (node (ref "U3") (pin "5") (pinfunction "GND_5") (pintype "bidirectional"))
      (node (ref "X1") (pin "5") (pinfunction "5_5") (pintype "passive"))
      (node (ref "X1") (pin "G1") (pinfunction "G1_G1") (pintype "passive"))
      (node (ref "X1") (pin "G2") (pinfunction "G2_G2") (pintype "passive"))
      (node (ref "XB1") (pin "10") (pinfunction "GND_10") (pintype "power_in"))
    )
    (net (code "47") (name "I1") (class "Default")
      (node (ref "ENC_2") (pin "2") (pinfunction "S_2") (pintype "passive"))
      (node (ref "R68") (pin "1") (pinfunction "1_1") (pintype "passive"))
      (node (ref "R71") (pin "2") (pinfunction "2_2") (pintype "passive"))
    )
    (net (code "48") (name "I2") (class "Default")
      (node (ref "ENC_1") (pin "2") (pinfunction "S_2") (pintype "passive"))
      (node (ref "R59") (pin "1") (pinfunction "1_1") (pintype "passive"))
      (node (ref "R62") (pin "2") (pinfunction "2_2") (pintype "passive"))
    )
    (net (code "49") (name "KLED_1") (class "Default")
      (node (ref "DIS1") (pin "80") (pinfunction "PD6_80") (pintype "bidirectional"))
      (node (ref "IC3") (pin "1") (pinfunction "I1_1") (pintype "input"))
    )
    (net (code "50") (name "KLED_2") (class "Default")
      (node (ref "DIS1") (pin "77") (pinfunction "PD7_77") (pintype "bidirectional"))
      (node (ref "IC3") (pin "2") (pinfunction "I2_2") (pintype "input"))
    )
    (net (code "51") (name "KLED_3") (class "Default")
      (node (ref "DIS1") (pin "40") (pinfunction "PD8_40") (pintype "bidirectional"))
      (node (ref "IC3") (pin "3") (pinfunction "I3_3") (pintype "input"))
    )
    (net (code "52") (name "KLED_4") (class "Default")
      (node (ref "DIS1") (pin "41") (pinfunction "PD9_41") (pintype "bidirectional"))
      (node (ref "IC3") (pin "4") (pinfunction "I4_4") (pintype "input"))
    )
    (net (code "53") (name "KLED_5") (class "Default")
      (node (ref "DIS1") (pin "42") (pinfunction "PD10_42") (pintype "bidirectional"))
      (node (ref "IC3") (pin "5") (pinfunction "I5_5") (pintype "input"))
    )
    (net (code "54") (name "KLED_6") (class "Default")
      (node (ref "DIS1") (pin "43") (pinfunction "PD11_43") (pintype "bidirectional"))
      (node (ref "IC3") (pin "6") (pinfunction "I6_6") (pintype "input"))
    )
    (net (code "55") (name "KLED_7") (class "Default")
      (node (ref "DIS1") (pin "44") (pinfunction "PD12_44") (pintype "bidirectional"))
      (node (ref "IC3") (pin "7") (pinfunction "I7_7") (pintype "input"))
    )
    (net (code "56") (name "KLED_8") (class "Default")
      (node (ref "DIS1") (pin "45") (pinfunction "PD13_45") (pintype "bidirectional"))
      (node (ref "IC3") (pin "8") (pinfunction "I8_8") (pintype "input"))
    )
    (net (code "57") (name "K_0") (class "Default")
      (node (ref "D2") (pin "2") (pinfunction "CATHODE_2") (pintype "bidirectional"))
      (node (ref "D3") (pin "2") (pinfunction "CATHODE_2") (pintype "bidirectional"))
      (node (ref "IC3") (pin "18") (pinfunction "O1_18") (pintype "open_collector"))
    )
    (net (code "58") (name "K_1") (class "Default")
      (node (ref "D4") (pin "2") (pinfunction "CATHODE_2") (pintype "bidirectional"))
      (node (ref "D5") (pin "2") (pinfunction "CATHODE_2") (pintype "bidirectional"))
      (node (ref "IC3") (pin "17") (pinfunction "O2_17") (pintype "open_collector"))
    )
    (net (code "59") (name "K_2") (class "Default")
      (node (ref "D6") (pin "2") (pinfunction "CATHODE_2") (pintype "bidirectional"))
      (node (ref "D7") (pin "2") (pinfunction "CATHODE_2") (pintype "bidirectional"))
      (node (ref "IC3") (pin "16") (pinfunction "O3_16") (pintype "open_collector"))
    )
    (net (code "60") (name "K_3") (class "Default")
      (node (ref "D8") (pin "2") (pinfunction "CATHODE_2") (pintype "bidirectional"))
      (node (ref "D9") (pin "2") (pinfunction "CATHODE_2") (pintype "bidirectional"))
      (node (ref "IC3") (pin "15") (pinfunction "O4_15") (pintype "open_collector"))
    )
    (net (code "61") (name "K_4") (class "Default")
      (node (ref "D10") (pin "2") (pinfunction "CATHODE_2") (pintype "bidirectional"))
      (node (ref "D11") (pin "2") (pinfunction "CATHODE_2") (pintype "bidirectional"))
      (node (ref "IC3") (pin "14") (pinfunction "O5_14") (pintype "open_collector"))
    )
    (net (code "62") (name "K_5") (class "Default")
      (node (ref "D12") (pin "2") (pinfunction "CATHODE_2") (pintype "bidirectional"))
      (node (ref "D13") (pin "2") (pinfunction "CATHODE_2") (pintype "bidirectional"))
      (node (ref "IC3") (pin "13") (pinfunction "O6_13") (pintype "open_collector"))
    )
    (net (code "63") (name "K_6") (class "Default")
      (node (ref "D14") (pin "2") (pinfunction "CATHODE_2") (pintype "bidirectional"))
      (node (ref "D15") (pin "2") (pinfunction "CATHODE_2") (pintype "bidirectional"))
      (node (ref "IC3") (pin "12") (pinfunction "O7_12") (pintype "open_collector"))
    )
    (net (code "64") (name "K_7") (class "Default")
      (node (ref "D16") (pin "2") (pinfunction "CATHODE_2") (pintype "bidirectional"))
      (node (ref "D17") (pin "2") (pinfunction "CATHODE_2") (pintype "bidirectional"))
      (node (ref "IC3") (pin "11") (pinfunction "O8_11") (pintype "open_collector"))
    )
    (net (code "65") (name "MOTOR1_AUX") (class "Default")
      (node (ref "CN3") (pin "2") (pinfunction "A+_2") (pintype "bidirectional"))
      (node (ref "DIS1") (pin "25") (pinfunction "PE7_25") (pintype "bidirectional"))
      (node (ref "MOT_1") (pin "6") (pinfunction "S_6") (pintype "passive"))
    )
    (net (code "66") (name "MOTOR1_EN") (class "Default")
      (node (ref "CN3") (pin "3") (pinfunction "A-_3") (pintype "bidirectional"))
      (node (ref "DIS1") (pin "24") (pinfunction "PB2_24") (pintype "bidirectional"))
      (node (ref "MOT_1") (pin "2") (pinfunction "S_2") (pintype "passive"))
    )
    (net (code "67") (name "MOTOR2_AUX") (class "Default")
      (node (ref "CN4") (pin "2") (pinfunction "A+_2") (pintype "bidirectional"))
      (node (ref "DIS1") (pin "30") (pinfunction "PE12_30") (pintype "bidirectional"))
      (node (ref "MOT_2") (pin "6") (pinfunction "S_6") (pintype "passive"))
    )
    (net (code "68") (name "MOTOR2_EN") (class "Default")
      (node (ref "CN4") (pin "3") (pinfunction "A-_3") (pintype "bidirectional"))
      (node (ref "DIS1") (pin "31") (pinfunction "PE13_31") (pintype "bidirectional"))
      (node (ref "MOT_2") (pin "2") (pinfunction "S_2") (pintype "passive"))
    )
    (net (code "69") (name "MUX_A") (class "Default")
      (node (ref "DIS1") (pin "95") (pinfunction "PC8_95") (pintype "bidirectional"))
      (node (ref "IC1") (pin "10") (pinfunction "A_10") (pintype "input"))
      (node (ref "IC1B") (pin "10") (pinfunction "A_10") (pintype "input"))
      (node (ref "IC2") (pin "10") (pinfunction "A_10") (pintype "input"))
      (node (ref "IC2B") (pin "10") (pinfunction "A_10") (pintype "input"))
    )
    (net (code "70") (name "MUX_B") (class "Default")
      (node (ref "DIS1") (pin "96") (pinfunction "PC9_96") (pintype "bidirectional"))
      (node (ref "IC1") (pin "11") (pinfunction "B_11") (pintype "input"))
      (node (ref "IC1B") (pin "11") (pinfunction "B_11") (pintype "input"))
      (node (ref "IC2") (pin "11") (pinfunction "B_11") (pintype "input"))
      (node (ref "IC2B") (pin "11") (pinfunction "B_11") (pintype "input"))
    )
    (net (code "71") (name "MUX_C") (class "Default")
      (node (ref "DIS1") (pin "93") (pinfunction "PA8_93") (pintype "bidirectional"))
      (node (ref "IC1") (pin "14") (pinfunction "C_14") (pintype "input"))
      (node (ref "IC1B") (pin "14") (pinfunction "C_14") (pintype "input"))
      (node (ref "IC2") (pin "14") (pinfunction "C_14") (pintype "input"))
      (node (ref "IC2B") (pin "14") (pinfunction "C_14") (pintype "input"))
    )
    (net (code "72") (name "MUX_D") (class "Default")
      (node (ref "DIS1") (pin "94") (pinfunction "PA9_94") (pintype "bidirectional"))
      (node (ref "IC1") (pin "13") (pinfunction "D_13") (pintype "input"))
      (node (ref "IC1B") (pin "13") (pinfunction "D_13") (pintype "input"))
      (node (ref "IC2") (pin "13") (pinfunction "D_13") (pintype "input"))
      (node (ref "IC2B") (pin "13") (pinfunction "D_13") (pintype "input"))
    )
    (net (code "73") (name "MUX_INH") (class "Default")
      (node (ref "DIS1") (pin "91") (pinfunction "PA10_91") (pintype "bidirectional"))
      (node (ref "IC1") (pin "15") (pinfunction "INH_15") (pintype "input"))
      (node (ref "IC1B") (pin "15") (pinfunction "INH_15") (pintype "input"))
      (node (ref "IC2") (pin "15") (pinfunction "INH_15") (pintype "input"))
      (node (ref "IC2B") (pin "15") (pinfunction "INH_15") (pintype "input"))
    )
    (net (code "74") (name "Net-(C1-Pad+)") (class "Default")
      (node (ref "C1") (pin "+") (pinfunction "+_+") (pintype "passive"))
      (node (ref "D1") (pin "C") (pinfunction "C_C") (pintype "passive"))
      (node (ref "JP1") (pin "1") (pinfunction "1_1") (pintype "passive"))
      (node (ref "U1") (pin "IN") (pinfunction "IN_IN") (pintype "input"))
    )
    (net (code "75") (name "Net-(CN1B-S)") (class "Default")
      (node (ref "CN1") (pin "2") (pinfunction "S_2") (pintype "passive"))
      (node (ref "D1") (pin "A") (pinfunction "A_A") (pintype "passive"))
    )
    (net (code "76") (name "Net-(CN2B-S)") (class "Default")
      (node (ref "C30") (pin "+") (pinfunction "+_+") (pintype "passive"))
      (node (ref "CN2") (pin "2") (pinfunction "S_2") (pintype "passive"))
      (node (ref "JP3") (pin "2") (pinfunction "2_2") (pintype "passive"))
      (node (ref "L1") (pin "1") (pinfunction "1_1") (pintype "passive"))
    )
    (net (code "77") (name "Net-(D2-BLUE_CATHODE)") (class "Default")
      (node (ref "D2") (pin "4") (pinfunction "BLUE_CATHODE_4") (pintype "bidirectional"))
      (node (ref "R5") (pin "1") (pinfunction "1_1") (pintype "passive"))
    )
    (net (code "78") (name "Net-(D2-GREEN_CATHODE)") (class "Default")
      (node (ref "D2") (pin "3") (pinfunction "GREEN_CATHODE_3") (pintype "bidirectional"))
      (node (ref "R7") (pin "1") (pinfunction "1_1") (pintype "passive"))
    )
    (net (code "79") (name "Net-(D2-RED_CATHODE)") (class "Default")
      (node (ref "D2") (pin "1") (pinfunction "RED_CATHODE_1") (pintype "bidirectional"))
      (node (ref "R9") (pin "1") (pinfunction "1_1") (pintype "passive"))
    )
    (net (code "80") (name "Net-(D3-BLUE_CATHODE)") (class "Default")
      (node (ref "D3") (pin "4") (pinfunction "BLUE_CATHODE_4") (pintype "bidirectional"))
      (node (ref "R6") (pin "1") (pinfunction "1_1") (pintype "passive"))
    )
    (net (code "81") (name "Net-(D3-GREEN_CATHODE)") (class "Default")
      (node (ref "D3") (pin "3") (pinfunction "GREEN_CATHODE_3") (pintype "bidirectional"))
      (node (ref "R8") (pin "1") (pinfunction "1_1") (pintype "passive"))
    )
    (net (code "82") (name "Net-(D3-RED_CATHODE)") (class "Default")
      (node (ref "D3") (pin "1") (pinfunction "RED_CATHODE_1") (pintype "bidirectional"))
      (node (ref "R10") (pin "1") (pinfunction "1_1") (pintype "passive"))
    )
    (net (code "83") (name "Net-(D4-BLUE_CATHODE)") (class "Default")
      (node (ref "D4") (pin "4") (pinfunction "BLUE_CATHODE_4") (pintype "bidirectional"))
      (node (ref "R11") (pin "1") (pinfunction "1_1") (pintype "passive"))
    )
    (net (code "84") (name "Net-(D4-GREEN_CATHODE)") (class "Default")
      (node (ref "D4") (pin "3") (pinfunction "GREEN_CATHODE_3") (pintype "bidirectional"))
      (node (ref "R13") (pin "1") (pinfunction "1_1") (pintype "passive"))
    )
    (net (code "85") (name "Net-(D4-RED_CATHODE)") (class "Default")
      (node (ref "D4") (pin "1") (pinfunction "RED_CATHODE_1") (pintype "bidirectional"))
      (node (ref "R17") (pin "1") (pinfunction "1_1") (pintype "passive"))
    )
    (net (code "86") (name "Net-(D5-BLUE_CATHODE)") (class "Default")
      (node (ref "D5") (pin "4") (pinfunction "BLUE_CATHODE_4") (pintype "bidirectional"))
      (node (ref "R12") (pin "1") (pinfunction "1_1") (pintype "passive"))
    )
    (net (code "87") (name "Net-(D5-GREEN_CATHODE)") (class "Default")
      (node (ref "D5") (pin "3") (pinfunction "GREEN_CATHODE_3") (pintype "bidirectional"))
      (node (ref "R16") (pin "1") (pinfunction "1_1") (pintype "passive"))
    )
    (net (code "88") (name "Net-(D5-RED_CATHODE)") (class "Default")
      (node (ref "D5") (pin "1") (pinfunction "RED_CATHODE_1") (pintype "bidirectional"))
      (node (ref "R18") (pin "1") (pinfunction "1_1") (pintype "passive"))
    )
    (net (code "89") (name "Net-(D6-BLUE_CATHODE)") (class "Default")
      (node (ref "D6") (pin "4") (pinfunction "BLUE_CATHODE_4") (pintype "bidirectional"))
      (node (ref "R19") (pin "1") (pinfunction "1_1") (pintype "passive"))
    )
    (net (code "90") (name "Net-(D6-GREEN_CATHODE)") (class "Default")
      (node (ref "D6") (pin "3") (pinfunction "GREEN_CATHODE_3") (pintype "bidirectional"))
      (node (ref "R21") (pin "1") (pinfunction "1_1") (pintype "passive"))
    )
    (net (code "91") (name "Net-(D6-RED_CATHODE)") (class "Default")
      (node (ref "D6") (pin "1") (pinfunction "RED_CATHODE_1") (pintype "bidirectional"))
      (node (ref "R23") (pin "1") (pinfunction "1_1") (pintype "passive"))
    )
    (net (code "92") (name "Net-(D7-BLUE_CATHODE)") (class "Default")
      (node (ref "D7") (pin "4") (pinfunction "BLUE_CATHODE_4") (pintype "bidirectional"))
      (node (ref "R20") (pin "1") (pinfunction "1_1") (pintype "passive"))
    )
    (net (code "93") (name "Net-(D7-GREEN_CATHODE)") (class "Default")
      (node (ref "D7") (pin "3") (pinfunction "GREEN_CATHODE_3") (pintype "bidirectional"))
      (node (ref "R22") (pin "1") (pinfunction "1_1") (pintype "passive"))
    )
    (net (code "94") (name "Net-(D7-RED_CATHODE)") (class "Default")
      (node (ref "D7") (pin "1") (pinfunction "RED_CATHODE_1") (pintype "bidirectional"))
      (node (ref "R24") (pin "1") (pinfunction "1_1") (pintype "passive"))
    )
    (net (code "95") (name "Net-(D8-BLUE_CATHODE)") (class "Default")
      (node (ref "D8") (pin "4") (pinfunction "BLUE_CATHODE_4") (pintype "bidirectional"))
      (node (ref "R25") (pin "1") (pinfunction "1_1") (pintype "passive"))
    )
    (net (code "96") (name "Net-(D8-GREEN_CATHODE)") (class "Default")
      (node (ref "D8") (pin "3") (pinfunction "GREEN_CATHODE_3") (pintype "bidirectional"))
      (node (ref "R27") (pin "1") (pinfunction "1_1") (pintype "passive"))
    )
    (net (code "97") (name "Net-(D8-RED_CATHODE)") (class "Default")
      (node (ref "D8") (pin "1") (pinfunction "RED_CATHODE_1") (pintype "bidirectional"))
      (node (ref "R29") (pin "1") (pinfunction "1_1") (pintype "passive"))
    )
    (net (code "98") (name "Net-(D9-BLUE_CATHODE)") (class "Default")
      (node (ref "D9") (pin "4") (pinfunction "BLUE_CATHODE_4") (pintype "bidirectional"))
      (node (ref "R26") (pin "1") (pinfunction "1_1") (pintype "passive"))
    )
    (net (code "99") (name "Net-(D9-GREEN_CATHODE)") (class "Default")
      (node (ref "D9") (pin "3") (pinfunction "GREEN_CATHODE_3") (pintype "bidirectional"))
      (node (ref "R28") (pin "1") (pinfunction "1_1") (pintype "passive"))
    )
    (net (code "100") (name "Net-(D9-RED_CATHODE)") (class "Default")
      (node (ref "D9") (pin "1") (pinfunction "RED_CATHODE_1") (pintype "bidirectional"))
      (node (ref "R30") (pin "1") (pinfunction "1_1") (pintype "passive"))
    )
    (net (code "101") (name "Net-(D10-BLUE_CATHODE)") (class "Default")
      (node (ref "D10") (pin "4") (pinfunction "BLUE_CATHODE_4") (pintype "bidirectional"))
      (node (ref "R32") (pin "1") (pinfunction "1_1") (pintype "passive"))
    )
    (net (code "102") (name "Net-(D10-GREEN_CATHODE)") (class "Default")
      (node (ref "D10") (pin "3") (pinfunction "GREEN_CATHODE_3") (pintype "bidirectional"))
      (node (ref "R35") (pin "1") (pinfunction "1_1") (pintype "passive"))
    )
    (net (code "103") (name "Net-(D10-RED_CATHODE)") (class "Default")
      (node (ref "D10") (pin "1") (pinfunction "RED_CATHODE_1") (pintype "bidirectional"))
      (node (ref "R37") (pin "1") (pinfunction "1_1") (pintype "passive"))
    )
    (net (code "104") (name "Net-(D11-BLUE_CATHODE)") (class "Default")
      (node (ref "D11") (pin "4") (pinfunction "BLUE_CATHODE_4") (pintype "bidirectional"))
      (node (ref "R34") (pin "1") (pinfunction "1_1") (pintype "passive"))
    )
    (net (code "105") (name "Net-(D11-GREEN_CATHODE)") (class "Default")
      (node (ref "D11") (pin "3") (pinfunction "GREEN_CATHODE_3") (pintype "bidirectional"))
      (node (ref "R36") (pin "1") (pinfunction "1_1") (pintype "passive"))
    )
    (net (code "106") (name "Net-(D11-RED_CATHODE)") (class "Default")
      (node (ref "D11") (pin "1") (pinfunction "RED_CATHODE_1") (pintype "bidirectional"))
      (node (ref "R38") (pin "1") (pinfunction "1_1") (pintype "passive"))
    )
    (net (code "107") (name "Net-(D12-BLUE_CATHODE)") (class "Default")
      (node (ref "D12") (pin "4") (pinfunction "BLUE_CATHODE_4") (pintype "bidirectional"))
      (node (ref "R39") (pin "1") (pinfunction "1_1") (pintype "passive"))
    )
    (net (code "108") (name "Net-(D12-GREEN_CATHODE)") (class "Default")
      (node (ref "D12") (pin "3") (pinfunction "GREEN_CATHODE_3") (pintype "bidirectional"))
      (node (ref "R41") (pin "1") (pinfunction "1_1") (pintype "passive"))
    )
    (net (code "109") (name "Net-(D12-RED_CATHODE)") (class "Default")
      (node (ref "D12") (pin "1") (pinfunction "RED_CATHODE_1") (pintype "bidirectional"))
      (node (ref "R43") (pin "1") (pinfunction "1_1") (pintype "passive"))
    )
    (net (code "110") (name "Net-(D13-BLUE_CATHODE)") (class "Default")
      (node (ref "D13") (pin "4") (pinfunction "BLUE_CATHODE_4") (pintype "bidirectional"))
      (node (ref "R40") (pin "1") (pinfunction "1_1") (pintype "passive"))
    )
    (net (code "111") (name "Net-(D13-GREEN_CATHODE)") (class "Default")
      (node (ref "D13") (pin "3") (pinfunction "GREEN_CATHODE_3") (pintype "bidirectional"))
      (node (ref "R42") (pin "1") (pinfunction "1_1") (pintype "passive"))
    )
    (net (code "112") (name "Net-(D13-RED_CATHODE)") (class "Default")
      (node (ref "D13") (pin "1") (pinfunction "RED_CATHODE_1") (pintype "bidirectional"))
      (node (ref "R44") (pin "1") (pinfunction "1_1") (pintype "passive"))
    )
    (net (code "113") (name "Net-(D14-BLUE_CATHODE)") (class "Default")
      (node (ref "D14") (pin "4") (pinfunction "BLUE_CATHODE_4") (pintype "bidirectional"))
      (node (ref "R45") (pin "1") (pinfunction "1_1") (pintype "passive"))
    )
    (net (code "114") (name "Net-(D14-GREEN_CATHODE)") (class "Default")
      (node (ref "D14") (pin "3") (pinfunction "GREEN_CATHODE_3") (pintype "bidirectional"))
      (node (ref "R47") (pin "1") (pinfunction "1_1") (pintype "passive"))
    )
    (net (code "115") (name "Net-(D14-RED_CATHODE)") (class "Default")
      (node (ref "D14") (pin "1") (pinfunction "RED_CATHODE_1") (pintype "bidirectional"))
      (node (ref "R49") (pin "1") (pinfunction "1_1") (pintype "passive"))
    )
    (net (code "116") (name "Net-(D15-BLUE_CATHODE)") (class "Default")
      (node (ref "D15") (pin "4") (pinfunction "BLUE_CATHODE_4") (pintype "bidirectional"))
      (node (ref "R46") (pin "1") (pinfunction "1_1") (pintype "passive"))
    )
    (net (code "117") (name "Net-(D15-GREEN_CATHODE)") (class "Default")
      (node (ref "D15") (pin "3") (pinfunction "GREEN_CATHODE_3") (pintype "bidirectional"))
      (node (ref "R48") (pin "1") (pinfunction "1_1") (pintype "passive"))
    )
    (net (code "118") (name "Net-(D15-RED_CATHODE)") (class "Default")
      (node (ref "D15") (pin "1") (pinfunction "RED_CATHODE_1") (pintype "bidirectional"))
      (node (ref "R50") (pin "1") (pinfunction "1_1") (pintype "passive"))
    )
    (net (code "119") (name "Net-(D16-BLUE_CATHODE)") (class "Default")
      (node (ref "D16") (pin "4") (pinfunction "BLUE_CATHODE_4") (pintype "bidirectional"))
      (node (ref "R51") (pin "1") (pinfunction "1_1") (pintype "passive"))
    )
    (net (code "120") (name "Net-(D16-GREEN_CATHODE)") (class "Default")
      (node (ref "D16") (pin "3") (pinfunction "GREEN_CATHODE_3") (pintype "bidirectional"))
      (node (ref "R53") (pin "1") (pinfunction "1_1") (pintype "passive"))
    )
    (net (code "121") (name "Net-(D16-RED_CATHODE)") (class "Default")
      (node (ref "D16") (pin "1") (pinfunction "RED_CATHODE_1") (pintype "bidirectional"))
      (node (ref "R55") (pin "1") (pinfunction "1_1") (pintype "passive"))
    )
    (net (code "122") (name "Net-(D17-BLUE_CATHODE)") (class "Default")
      (node (ref "D17") (pin "4") (pinfunction "BLUE_CATHODE_4") (pintype "bidirectional"))
      (node (ref "R52") (pin "1") (pinfunction "1_1") (pintype "passive"))
    )
    (net (code "123") (name "Net-(D17-GREEN_CATHODE)") (class "Default")
      (node (ref "D17") (pin "3") (pinfunction "GREEN_CATHODE_3") (pintype "bidirectional"))
      (node (ref "R54") (pin "1") (pinfunction "1_1") (pintype "passive"))
    )
    (net (code "124") (name "Net-(D17-RED_CATHODE)") (class "Default")
      (node (ref "D17") (pin "1") (pinfunction "RED_CATHODE_1") (pintype "bidirectional"))
      (node (ref "R56") (pin "1") (pinfunction "1_1") (pintype "passive"))
    )
    (net (code "125") (name "Net-(IC4A-C1+)") (class "Default")
      (node (ref "C34") (pin "+") (pinfunction "+_+") (pintype "passive"))
      (node (ref "IC4") (pin "1") (pinfunction "C1+_1") (pintype "bidirectional"))
    )
    (net (code "126") (name "Net-(IC4A-C1-)") (class "Default")
      (node (ref "C34") (pin "-") (pinfunction "-_-") (pintype "passive"))
      (node (ref "IC4") (pin "3") (pinfunction "C1-_3") (pintype "bidirectional"))
    )
    (net (code "127") (name "Net-(IC4A-C2+)") (class "Default")
      (node (ref "C35") (pin "+") (pinfunction "+_+") (pintype "passive"))
      (node (ref "IC4") (pin "4") (pinfunction "C2+_4") (pintype "bidirectional"))
    )
    (net (code "128") (name "Net-(IC4A-C2-)") (class "Default")
      (node (ref "C35") (pin "-") (pinfunction "-_-") (pintype "passive"))
      (node (ref "IC4") (pin "5") (pinfunction "C2-_5") (pintype "bidirectional"))
    )
    (net (code "129") (name "Net-(IC4A-R1OUT)") (class "Default")
      (node (ref "IC4") (pin "12") (pinfunction "R1OUT_12") (pintype "output"))
      (node (ref "JP8") (pin "1") (pinfunction "1_1") (pintype "passive"))
    )
    (net (code "130") (name "Net-(IC4A-T1IN)") (class "Default")
      (node (ref "IC4") (pin "11") (pinfunction "T1IN_11") (pintype "input"))
      (node (ref "JP8") (pin "3") (pinfunction "3_3") (pintype "passive"))
    )
    (net (code "131") (name "Net-(IC4A-V+)") (class "Default")
      (node (ref "C37") (pin "+") (pinfunction "+_+") (pintype "passive"))
      (node (ref "IC4") (pin "2") (pinfunction "V+_2") (pintype "bidirectional"))
    )
    (net (code "132") (name "Net-(IC4A-V-)") (class "Default")
      (node (ref "C38") (pin "-") (pinfunction "-_-") (pintype "passive"))
      (node (ref "IC4") (pin "6") (pinfunction "V-_6") (pintype "bidirectional"))
    )
    (net (code "133") (name "Net-(J1A-S)") (class "Default")
      (node (ref "C32") (pin "1") (pinfunction "1_1") (pintype "passive"))
      (node (ref "J1") (pin "1") (pinfunction "S_1") (pintype "passive"))
      (node (ref "R77") (pin "2") (pinfunction "2_2") (pintype "passive"))
      (node (ref "R78") (pin "2") (pinfunction "2_2") (pintype "passive"))
    )
    (net (code "134") (name "Net-(J2A-S)") (class "Default")
      (node (ref "C33") (pin "1") (pinfunction "1_1") (pintype "passive"))
      (node (ref "J2") (pin "1") (pinfunction "S_1") (pintype "passive"))
      (node (ref "R75") (pin "2") (pinfunction "2_2") (pintype "passive"))
      (node (ref "R76") (pin "2") (pinfunction "2_2") (pintype "passive"))
    )
    (net (code "135") (name "Net-(JP2-Pad1)") (class "Default")
      (node (ref "JP2") (pin "1") (pinfunction "1_1") (pintype "passive"))
      (node (ref "R2") (pin "2") (pinfunction "2_2") (pintype "passive"))
    )
    (net (code "136") (name "Net-(JP2-Pad6)") (class "Default")
      (node (ref "JP2") (pin "6") (pinfunction "6_6") (pintype "passive"))
      (node (ref "R1") (pin "2") (pinfunction "2_2") (pintype "passive"))
    )
    (net (code "137") (name "Net-(JP4-Pad1)") (class "Default")
      (node (ref "JP4") (pin "1") (pinfunction "1_1") (pintype "passive"))
      (node (ref "R57") (pin "2") (pinfunction "2_2") (pintype "passive"))
    )
    (net (code "138") (name "Net-(JP4-Pad3)") (class "Default")
      (node (ref "JP4") (pin "3") (pinfunction "3_3") (pintype "passive"))
      (node (ref "R58") (pin "2") (pinfunction "2_2") (pintype "passive"))
    )
    (net (code "139") (name "Net-(JP4-Pad5)") (class "Default")
      (node (ref "JP4") (pin "5") (pinfunction "5_5") (pintype "passive"))
      (node (ref "R59") (pin "2") (pinfunction "2_2") (pintype "passive"))
    )
    (net (code "140") (name "Net-(JP5-Pad2)") (class "Default")
      (node (ref "JP5") (pin "2") (pinfunction "2_2") (pintype "passive"))
      (node (ref "R63") (pin "1") (pinfunction "1_1") (pintype "passive"))
    )
    (net (code "141") (name "Net-(JP5-Pad4)") (class "Default")
      (node (ref "JP5") (pin "4") (pinfunction "4_4") (pintype "passive"))
      (node (ref "R64") (pin "1") (pinfunction "1_1") (pintype "passive"))
    )
    (net (code "142") (name "Net-(JP5-Pad6)") (class "Default")
      (node (ref "JP5") (pin "6") (pinfunction "6_6") (pintype "passive"))
      (node (ref "R65") (pin "1") (pinfunction "1_1") (pintype "passive"))
    )
    (net (code "143") (name "Net-(JP6-Pad1)") (class "Default")
      (node (ref "JP6") (pin "1") (pinfunction "1_1") (pintype "passive"))
      (node (ref "R66") (pin "2") (pinfunction "2_2") (pintype "passive"))
    )
    (net (code "144") (name "Net-(JP6-Pad3)") (class "Default")
      (node (ref "JP6") (pin "3") (pinfunction "3_3") (pintype "passive"))
      (node (ref "R67") (pin "2") (pinfunction "2_2") (pintype "passive"))
    )
    (net (code "145") (name "Net-(JP6-Pad5)") (class "Default")
      (node (ref "JP6") (pin "5") (pinfunction "5_5") (pintype "passive"))
      (node (ref "R68") (pin "2") (pinfunction "2_2") (pintype "passive"))
    )
    (net (code "146") (name "Net-(JP7-Pad2)") (class "Default")
      (node (ref "JP7") (pin "2") (pinfunction "2_2") (pintype "passive"))
      (node (ref "R72") (pin "1") (pinfunction "1_1") (pintype "passive"))
    )
    (net (code "147") (name "Net-(JP7-Pad4)") (class "Default")
      (node (ref "JP7") (pin "4") (pinfunction "4_4") (pintype "passive"))
      (node (ref "R73") (pin "1") (pinfunction "1_1") (pintype "passive"))
    )
    (net (code "148") (name "Net-(JP7-Pad6)") (class "Default")
      (node (ref "JP7") (pin "6") (pinfunction "6_6") (pintype "passive"))
      (node (ref "R74") (pin "1") (pinfunction "1_1") (pintype "passive"))
    )
    (net (code "149") (name "Net-(JP11-Pad1)") (class "Default")
      (node (ref "JP11") (pin "1") (pinfunction "1_1") (pintype "passive"))
      (node (ref "R83") (pin "2") (pinfunction "2_2") (pintype "passive"))
    )
    (net (code "150") (name "Net-(JP11-Pad3)") (class "Default")
      (node (ref "JP11") (pin "3") (pinfunction "3_3") (pintype "passive"))
      (node (ref "R84") (pin "1") (pinfunction "1_1") (pintype "passive"))
    )
    (net (code "151") (name "Net-(JP11-Pad5)") (class "Default")
      (node (ref "JP11") (pin "5") (pinfunction "5_5") (pintype "passive"))
      (node (ref "R85") (pin "2") (pinfunction "2_2") (pintype "passive"))
    )
    (net (code "152") (name "Net-(LED1-PadA)") (class "Default")
      (node (ref "LED1") (pin "A") (pinfunction "A_A") (pintype "passive"))
      (node (ref "R81") (pin "2") (pinfunction "2_2") (pintype "passive"))
    )
    (net (code "153") (name "Net-(LED2-PadA)") (class "Default")
      (node (ref "LED2") (pin "A") (pinfunction "A_A") (pintype "passive"))
      (node (ref "R82") (pin "1") (pinfunction "1_1") (pintype "passive"))
    )
    (net (code "154") (name "Net-(Q1-PadB)") (class "Default")
      (node (ref "Q1") (pin "B") (pinfunction "B_B") (pintype "passive"))
      (node (ref "R3") (pin "1") (pinfunction "1_1") (pintype "passive"))
    )
    (net (code "155") (name "Net-(Q1-PadC)") (class "Default")
      (node (ref "Q1") (pin "C") (pinfunction "C_C") (pintype "passive"))
      (node (ref "R11") (pin "2") (pinfunction "2_2") (pintype "passive"))
      (node (ref "R19") (pin "2") (pinfunction "2_2") (pintype "passive"))
      (node (ref "R25") (pin "2") (pinfunction "2_2") (pintype "passive"))
      (node (ref "R32") (pin "2") (pinfunction "2_2") (pintype "passive"))
      (node (ref "R39") (pin "2") (pinfunction "2_2") (pintype "passive"))
      (node (ref "R45") (pin "2") (pinfunction "2_2") (pintype "passive"))
      (node (ref "R5") (pin "2") (pinfunction "2_2") (pintype "passive"))
      (node (ref "R51") (pin "2") (pinfunction "2_2") (pintype "passive"))
    )
    (net (code "156") (name "Net-(Q2-PadB)") (class "Default")
      (node (ref "Q2") (pin "B") (pinfunction "B_B") (pintype "passive"))
      (node (ref "R4") (pin "1") (pinfunction "1_1") (pintype "passive"))
    )
    (net (code "157") (name "Net-(Q2-PadC)") (class "Default")
      (node (ref "Q2") (pin "C") (pinfunction "C_C") (pintype "passive"))
      (node (ref "R12") (pin "2") (pinfunction "2_2") (pintype "passive"))
      (node (ref "R20") (pin "2") (pinfunction "2_2") (pintype "passive"))
      (node (ref "R26") (pin "2") (pinfunction "2_2") (pintype "passive"))
      (node (ref "R34") (pin "2") (pinfunction "2_2") (pintype "passive"))
      (node (ref "R40") (pin "2") (pinfunction "2_2") (pintype "passive"))
      (node (ref "R46") (pin "2") (pinfunction "2_2") (pintype "passive"))
      (node (ref "R52") (pin "2") (pinfunction "2_2") (pintype "passive"))
      (node (ref "R6") (pin "2") (pinfunction "2_2") (pintype "passive"))
    )
    (net (code "158") (name "Net-(Q3-PadB)") (class "Default")
      (node (ref "Q3") (pin "B") (pinfunction "B_B") (pintype "passive"))
      (node (ref "R14") (pin "1") (pinfunction "1_1") (pintype "passive"))
    )
    (net (code "159") (name "Net-(Q3-PadC)") (class "Default")
      (node (ref "Q3") (pin "C") (pinfunction "C_C") (pintype "passive"))
      (node (ref "R13") (pin "2") (pinfunction "2_2") (pintype "passive"))
      (node (ref "R21") (pin "2") (pinfunction "2_2") (pintype "passive"))
      (node (ref "R27") (pin "2") (pinfunction "2_2") (pintype "passive"))
      (node (ref "R35") (pin "2") (pinfunction "2_2") (pintype "passive"))
      (node (ref "R41") (pin "2") (pinfunction "2_2") (pintype "passive"))
      (node (ref "R47") (pin "2") (pinfunction "2_2") (pintype "passive"))
      (node (ref "R53") (pin "2") (pinfunction "2_2") (pintype "passive"))
      (node (ref "R7") (pin "2") (pinfunction "2_2") (pintype "passive"))
    )
    (net (code "160") (name "Net-(Q4-PadB)") (class "Default")
      (node (ref "Q4") (pin "B") (pinfunction "B_B") (pintype "passive"))
      (node (ref "R15") (pin "1") (pinfunction "1_1") (pintype "passive"))
    )
    (net (code "161") (name "Net-(Q4-PadC)") (class "Default")
      (node (ref "Q4") (pin "C") (pinfunction "C_C") (pintype "passive"))
      (node (ref "R16") (pin "2") (pinfunction "2_2") (pintype "passive"))
      (node (ref "R22") (pin "2") (pinfunction "2_2") (pintype "passive"))
      (node (ref "R28") (pin "2") (pinfunction "2_2") (pintype "passive"))
      (node (ref "R36") (pin "2") (pinfunction "2_2") (pintype "passive"))
      (node (ref "R42") (pin "2") (pinfunction "2_2") (pintype "passive"))
      (node (ref "R48") (pin "2") (pinfunction "2_2") (pintype "passive"))
      (node (ref "R54") (pin "2") (pinfunction "2_2") (pintype "passive"))
      (node (ref "R8") (pin "2") (pinfunction "2_2") (pintype "passive"))
    )
    (net (code "162") (name "Net-(Q5-PadB)") (class "Default")
      (node (ref "Q5") (pin "B") (pinfunction "B_B") (pintype "passive"))
      (node (ref "R31") (pin "1") (pinfunction "1_1") (pintype "passive"))
    )
    (net (code "163") (name "Net-(Q5-PadC)") (class "Default")
      (node (ref "Q5") (pin "C") (pinfunction "C_C") (pintype "passive"))
      (node (ref "R17") (pin "2") (pinfunction "2_2") (pintype "passive"))
      (node (ref "R23") (pin "2") (pinfunction "2_2") (pintype "passive"))
      (node (ref "R29") (pin "2") (pinfunction "2_2") (pintype "passive"))
      (node (ref "R37") (pin "2") (pinfunction "2_2") (pintype "passive"))
      (node (ref "R43") (pin "2") (pinfunction "2_2") (pintype "passive"))
      (node (ref "R49") (pin "2") (pinfunction "2_2") (pintype "passive"))
      (node (ref "R55") (pin "2") (pinfunction "2_2") (pintype "passive"))
      (node (ref "R9") (pin "2") (pinfunction "2_2") (pintype "passive"))
    )
    (net (code "164") (name "Net-(Q6-PadB)") (class "Default")
      (node (ref "Q6") (pin "B") (pinfunction "B_B") (pintype "passive"))
      (node (ref "R33") (pin "1") (pinfunction "1_1") (pintype "passive"))
    )
    (net (code "165") (name "Net-(Q6-PadC)") (class "Default")
      (node (ref "Q6") (pin "C") (pinfunction "C_C") (pintype "passive"))
      (node (ref "R10") (pin "2") (pinfunction "2_2") (pintype "passive"))
      (node (ref "R18") (pin "2") (pinfunction "2_2") (pintype "passive"))
      (node (ref "R24") (pin "2") (pinfunction "2_2") (pintype "passive"))
      (node (ref "R30") (pin "2") (pinfunction "2_2") (pintype "passive"))
      (node (ref "R38") (pin "2") (pinfunction "2_2") (pintype "passive"))
      (node (ref "R44") (pin "2") (pinfunction "2_2") (pintype "passive"))
      (node (ref "R50") (pin "2") (pinfunction "2_2") (pintype "passive"))
      (node (ref "R56") (pin "2") (pinfunction "2_2") (pintype "passive"))
    )
    (net (code "166") (name "Net-(R80-Pad1)") (class "Default")
      (node (ref "R80") (pin "1") (pinfunction "1_1") (pintype "passive"))
      (node (ref "X1") (pin "6") (pinfunction "6_6") (pintype "passive"))
    )
    (net (code "167") (name "Net-(R86-Pad2)") (class "Default")
      (node (ref "R86") (pin "2") (pinfunction "2_2") (pintype "passive"))
      (node (ref "X1") (pin "4") (pinfunction "4_4") (pintype "passive"))
    )
    (net (code "168") (name "Net-(U3-DE)") (class "Default")
      (node (ref "JP9") (pin "3") (pinfunction "3_3") (pintype "passive"))
      (node (ref "R79") (pin "2") (pinfunction "2_2") (pintype "passive"))
      (node (ref "U3") (pin "2") (pinfunction "RE/_2") (pintype "input"))
      (node (ref "U3") (pin "3") (pinfunction "DE_3") (pintype "input"))
    )
    (net (code "169") (name "Net-(U3-DI)") (class "Default")
      (node (ref "JP9") (pin "1") (pinfunction "1_1") (pintype "passive"))
      (node (ref "U3") (pin "4") (pinfunction "DI_4") (pintype "input"))
    )
    (net (code "170") (name "Net-(U3-RO)") (class "Default")
      (node (ref "JP9") (pin "5") (pinfunction "5_5") (pintype "passive"))
      (node (ref "U3") (pin "1") (pinfunction "RO_1") (pintype "output"))
    )
    (net (code "171") (name "Net-(XB1-ASSOC{slash}AD5{slash}DIO5)") (class "Default")
      (node (ref "R82") (pin "2") (pinfunction "2_2") (pintype "passive"))
      (node (ref "XB1") (pin "15") (pinfunction "ASSOC/AD5/DIO5_15") (pintype "bidirectional"))
    )
    (net (code "172") (name "Net-(XB1-PWM0{slash}RSSI)") (class "Default")
      (node (ref "R81") (pin "1") (pinfunction "1_1") (pintype "passive"))
      (node (ref "XB1") (pin "6") (pinfunction "PWM0/RSSI_6") (pintype "output"))
    )
    (net (code "173") (name "P1") (class "Default")
      (node (ref "DIS1") (pin "36") (pinfunction "PB12_36") (pintype "bidirectional"))
      (node (ref "P1") (pin "1") (pinfunction "P1_1") (pintype "passive"))
      (node (ref "P1") (pin "2") (pinfunction "P_2") (pintype "passive"))
      (node (ref "R87") (pin "2") (pinfunction "2_2") (pintype "passive"))
    )
    (net (code "174") (name "P2") (class "Default")
      (node (ref "DIS1") (pin "37") (pinfunction "PB13_37") (pintype "bidirectional"))
      (node (ref "P2") (pin "1") (pinfunction "P1_1") (pintype "passive"))
      (node (ref "P2") (pin "2") (pinfunction "P_2") (pintype "passive"))
      (node (ref "R88") (pin "2") (pinfunction "2_2") (pintype "passive"))
    )
    (net (code "175") (name "PWM_CH1_N") (class "Default")
      (node (ref "CN3") (pin "5") (pinfunction "B-_5") (pintype "bidirectional"))
      (node (ref "DIS1") (pin "26") (pinfunction "PE8_26") (pintype "bidirectional"))
      (node (ref "MOT_1") (pin "3") (pinfunction "S_3") (pintype "passive"))
    )
    (net (code "176") (name "PWM_CH1_P") (class "Default")
      (node (ref "CN3") (pin "6") (pinfunction "B+_6") (pintype "bidirectional"))
      (node (ref "DIS1") (pin "27") (pinfunction "PE9_27") (pintype "bidirectional"))
      (node (ref "MOT_1") (pin "4") (pinfunction "S_4") (pintype "passive"))
    )
    (net (code "177") (name "PWM_CH2_N") (class "Default")
      (node (ref "CN4") (pin "5") (pinfunction "B-_5") (pintype "bidirectional"))
      (node (ref "DIS1") (pin "28") (pinfunction "PE10_28") (pintype "bidirectional"))
      (node (ref "MOT_2") (pin "3") (pinfunction "S_3") (pintype "passive"))
    )
    (net (code "178") (name "PWM_CH2_P") (class "Default")
      (node (ref "CN4") (pin "6") (pinfunction "B+_6") (pintype "bidirectional"))
      (node (ref "DIS1") (pin "29") (pinfunction "PE11_29") (pintype "bidirectional"))
      (node (ref "MOT_2") (pin "4") (pinfunction "S_4") (pintype "passive"))
    )
    (net (code "179") (name "RXD") (class "Default")
      (node (ref "IC4") (pin "13") (pinfunction "R1IN_13") (pintype "input"))
      (node (ref "X1") (pin "3") (pinfunction "3_3") (pintype "passive"))
    )
    (net (code "180") (name "TRIGGER_MUX") (class "Default")
      (node (ref "DIS1") (pin "70") (pinfunction "PB9_70") (pintype "bidirectional"))
      (node (ref "IC1") (pin "1") (pinfunction "X_1") (pintype "output"))
      (node (ref "IC1B") (pin "1") (pinfunction "X_1") (pintype "output"))
    )
    (net (code "181") (name "TRIGGER_U1") (class "Default")
      (node (ref "IC1") (pin "9") (pinfunction "X0_9") (pintype "input"))
      (node (ref "IC1B") (pin "9") (pinfunction "X0_9") (pintype "input"))
      (node (ref "SN1") (pin "2") (pinfunction "S_2") (pintype "passive"))
    )
    (net (code "182") (name "TRIGGER_U2") (class "Default")
      (node (ref "IC1") (pin "8") (pinfunction "X1_8") (pintype "input"))
      (node (ref "IC1B") (pin "8") (pinfunction "X1_8") (pintype "input"))
      (node (ref "SN2") (pin "2") (pinfunction "S_2") (pintype "passive"))
    )
    (net (code "183") (name "TRIGGER_U3") (class "Default")
      (node (ref "IC1") (pin "7") (pinfunction "X2_7") (pintype "input"))
      (node (ref "IC1B") (pin "7") (pinfunction "X2_7") (pintype "input"))
      (node (ref "SN3") (pin "2") (pinfunction "S_2") (pintype "passive"))
    )
    (net (code "184") (name "TRIGGER_U4") (class "Default")
      (node (ref "IC1") (pin "6") (pinfunction "X3_6") (pintype "input"))
      (node (ref "IC1B") (pin "6") (pinfunction "X3_6") (pintype "input"))
      (node (ref "SN4") (pin "2") (pinfunction "S_2") (pintype "passive"))
    )
    (net (code "185") (name "TRIGGER_U5") (class "Default")
      (node (ref "IC1") (pin "5") (pinfunction "X4_5") (pintype "input"))
      (node (ref "IC1B") (pin "5") (pinfunction "X4_5") (pintype "input"))
      (node (ref "SN5") (pin "2") (pinfunction "S_2") (pintype "passive"))
    )
    (net (code "186") (name "TRIGGER_U6") (class "Default")
      (node (ref "IC1") (pin "4") (pinfunction "X5_4") (pintype "input"))
      (node (ref "IC1B") (pin "4") (pinfunction "X5_4") (pintype "input"))
      (node (ref "SN6") (pin "2") (pinfunction "S_2") (pintype "passive"))
    )
    (net (code "187") (name "TRIGGER_U7") (class "Default")
      (node (ref "IC1") (pin "3") (pinfunction "X6_3") (pintype "input"))
      (node (ref "IC1B") (pin "3") (pinfunction "X6_3") (pintype "input"))
      (node (ref "SN7") (pin "2") (pinfunction "S_2") (pintype "passive"))
    )
    (net (code "188") (name "TRIGGER_U8") (class "Default")
      (node (ref "IC1") (pin "2") (pinfunction "X7_2") (pintype "input"))
      (node (ref "IC1B") (pin "2") (pinfunction "X7_2") (pintype "input"))
      (node (ref "SN8") (pin "2") (pinfunction "S_2") (pintype "passive"))
    )
    (net (code "189") (name "TRIGGER_U9") (class "Default")
      (node (ref "IC1") (pin "23") (pinfunction "X8_23") (pintype "input"))
      (node (ref "IC1B") (pin "23") (pinfunction "X8_23") (pintype "input"))
      (node (ref "SN9") (pin "2") (pinfunction "S_2") (pintype "passive"))
    )
    (net (code "190") (name "TRIGGER_U10") (class "Default")
      (node (ref "IC1") (pin "22") (pinfunction "X9_22") (pintype "input"))
      (node (ref "IC1B") (pin "22") (pinfunction "X9_22") (pintype "input"))
      (node (ref "SN10") (pin "2") (pinfunction "S_2") (pintype "passive"))
    )
    (net (code "191") (name "TRIGGER_U11") (class "Default")
      (node (ref "IC1") (pin "21") (pinfunction "X10_21") (pintype "input"))
      (node (ref "IC1B") (pin "21") (pinfunction "X10_21") (pintype "input"))
      (node (ref "SN11") (pin "2") (pinfunction "S_2") (pintype "passive"))
    )
    (net (code "192") (name "TRIGGER_U12") (class "Default")
      (node (ref "IC1") (pin "20") (pinfunction "X11_20") (pintype "input"))
      (node (ref "IC1B") (pin "20") (pinfunction "X11_20") (pintype "input"))
      (node (ref "SN12") (pin "2") (pinfunction "S_2") (pintype "passive"))
    )
    (net (code "193") (name "TRIGGER_U13") (class "Default")
      (node (ref "IC1") (pin "19") (pinfunction "X12_19") (pintype "input"))
      (node (ref "IC1B") (pin "19") (pinfunction "X12_19") (pintype "input"))
      (node (ref "SN13") (pin "2") (pinfunction "S_2") (pintype "passive"))
    )
    (net (code "194") (name "TRIGGER_U14") (class "Default")
      (node (ref "IC1") (pin "18") (pinfunction "X13_18") (pintype "input"))
      (node (ref "IC1B") (pin "18") (pinfunction "X13_18") (pintype "input"))
      (node (ref "SN14") (pin "2") (pinfunction "S_2") (pintype "passive"))
    )
    (net (code "195") (name "TRIGGER_U15") (class "Default")
      (node (ref "IC1") (pin "17") (pinfunction "X14_17") (pintype "input"))
      (node (ref "IC1B") (pin "17") (pinfunction "X14_17") (pintype "input"))
      (node (ref "SN15") (pin "2") (pinfunction "S_2") (pintype "passive"))
    )
    (net (code "196") (name "TRIGGER_U16") (class "Default")
      (node (ref "IC1") (pin "16") (pinfunction "X15_16") (pintype "input"))
      (node (ref "IC1B") (pin "16") (pinfunction "X15_16") (pintype "input"))
      (node (ref "SN16") (pin "2") (pinfunction "S_2") (pintype "passive"))
    )
    (net (code "197") (name "TR_S1_BLUE") (class "Default")
      (node (ref "DIS1") (pin "84") (pinfunction "PD2_84") (pintype "bidirectional"))
      (node (ref "R3") (pin "2") (pinfunction "2_2") (pintype "passive"))
    )
    (net (code "198") (name "TR_S1_GREEN") (class "Default")
      (node (ref "DIS1") (pin "83") (pinfunction "PD1_83") (pintype "bidirectional"))
      (node (ref "R14") (pin "2") (pinfunction "2_2") (pintype "passive"))
    )
    (net (code "199") (name "TR_S1_RED") (class "Default")
      (node (ref "DIS1") (pin "86") (pinfunction "PD0_86") (pintype "bidirectional"))
      (node (ref "R31") (pin "2") (pinfunction "2_2") (pintype "passive"))
    )
    (net (code "200") (name "TR_S2_BLUE") (class "Default")
      (node (ref "DIS1") (pin "79") (pinfunction "PD5_79") (pintype "bidirectional"))
      (node (ref "R4") (pin "2") (pinfunction "2_2") (pintype "passive"))
    )
    (net (code "201") (name "TR_S2_GREEN") (class "Default")
      (node (ref "DIS1") (pin "82") (pinfunction "PD4_82") (pintype "bidirectional"))
      (node (ref "R15") (pin "2") (pinfunction "2_2") (pintype "passive"))
    )
    (net (code "202") (name "TR_S2_RED") (class "Default")
      (node (ref "DIS1") (pin "81") (pinfunction "PD3_81") (pintype "bidirectional"))
      (node (ref "R33") (pin "2") (pinfunction "2_2") (pintype "passive"))
    )
    (net (code "203") (name "TXD") (class "Default")
      (node (ref "IC4") (pin "14") (pinfunction "T1OUT_14") (pintype "output"))
      (node (ref "X1") (pin "2") (pinfunction "2_2") (pintype "passive"))
    )
    (net (code "204") (name "unconnected-(DIS1A-BOOT0-Pad71)") (class "Default")
      (node (ref "DIS1") (pin "71") (pinfunction "BOOT0_71") (pintype "bidirectional"))
    )
    (net (code "205") (name "unconnected-(DIS1A-NC-Pad48)") (class "Default")
      (node (ref "DIS1") (pin "48") (pinfunction "NC_48") (pintype "bidirectional"))
    )
    (net (code "206") (name "unconnected-(DIS1A-NRST-Pad6)") (class "Default")
      (node (ref "DIS1") (pin "6") (pinfunction "NRST_6") (pintype "bidirectional"))
    )
    (net (code "207") (name "unconnected-(DIS1A-PA13-Pad92)") (class "Default")
      (node (ref "DIS1") (pin "92") (pinfunction "PA13_92") (pintype "bidirectional"))
    )
    (net (code "208") (name "unconnected-(DIS1A-PA14-Pad89)") (class "Default")
      (node (ref "DIS1") (pin "89") (pinfunction "PA14_89") (pintype "bidirectional"))
    )
    (net (code "209") (name "unconnected-(DIS1A-PA15-Pad90)") (class "Default")
      (node (ref "DIS1") (pin "90") (pinfunction "PA15_90") (pintype "bidirectional"))
    )
    (net (code "210") (name "unconnected-(DIS1A-PB0-Pad22)") (class "Default")
      (node (ref "DIS1") (pin "22") (pinfunction "PB0_22") (pintype "bidirectional"))
    )
    (net (code "211") (name "unconnected-(DIS1A-PB1-Pad21)") (class "Default")
      (node (ref "DIS1") (pin "21") (pinfunction "PB1_21") (pintype "bidirectional"))
    )
    (net (code "212") (name "unconnected-(DIS1A-PB3-Pad78)") (class "Default")
      (node (ref "DIS1") (pin "78") (pinfunction "PB3_78") (pintype "bidirectional"))
    )
    (net (code "213") (name "unconnected-(DIS1A-PB4-Pad75)") (class "Default")
      (node (ref "DIS1") (pin "75") (pinfunction "PB4_75") (pintype "bidirectional"))
    )
    (net (code "214") (name "unconnected-(DIS1A-PB8-Pad69)") (class "Default")
      (node (ref "DIS1") (pin "69") (pinfunction "PB8_69") (pintype "bidirectional"))
    )
    (net (code "215") (name "unconnected-(DIS1A-PB15-Pad39)") (class "Default")
      (node (ref "DIS1") (pin "39") (pinfunction "PB15_39") (pintype "bidirectional"))
    )
    (net (code "216") (name "unconnected-(DIS1A-PC0-Pad8)") (class "Default")
      (node (ref "DIS1") (pin "8") (pinfunction "PC0_8") (pintype "bidirectional"))
    )
    (net (code "217") (name "unconnected-(DIS1A-PC1-Pad7)") (class "Default")
      (node (ref "DIS1") (pin "7") (pinfunction "PC1_7") (pintype "bidirectional"))
    )
    (net (code "218") (name "unconnected-(DIS1A-PC2-Pad10)") (class "Default")
      (node (ref "DIS1") (pin "10") (pinfunction "PC2_10") (pintype "bidirectional"))
    )
    (net (code "219") (name "unconnected-(DIS1A-PC3-Pad9)") (class "Default")
      (node (ref "DIS1") (pin "9") (pinfunction "PC3_9") (pintype "bidirectional"))
    )
    (net (code "220") (name "unconnected-(DIS1A-PC5-Pad19)") (class "Default")
      (node (ref "DIS1") (pin "19") (pinfunction "PC5_19") (pintype "bidirectional"))
    )
    (net (code "221") (name "unconnected-(DIS1A-PC6-Pad97)") (class "Default")
      (node (ref "DIS1") (pin "97") (pinfunction "PC6_97") (pintype "bidirectional"))
    )
    (net (code "222") (name "unconnected-(DIS1A-PC7-Pad98)") (class "Default")
      (node (ref "DIS1") (pin "98") (pinfunction "PC7_98") (pintype "bidirectional"))
    )
    (net (code "223") (name "unconnected-(DIS1A-PC10-Pad87)") (class "Default")
      (node (ref "DIS1") (pin "87") (pinfunction "PC10_87") (pintype "bidirectional"))
    )
    (net (code "224") (name "unconnected-(DIS1A-PC11-Pad88)") (class "Default")
      (node (ref "DIS1") (pin "88") (pinfunction "PC11_88") (pintype "bidirectional"))
    )
    (net (code "225") (name "unconnected-(DIS1A-PC12-Pad85)") (class "Default")
      (node (ref "DIS1") (pin "85") (pinfunction "PC12_85") (pintype "bidirectional"))
    )
    (net (code "226") (name "unconnected-(DIS1A-PC13-Pad62)") (class "Default")
      (node (ref "DIS1") (pin "62") (pinfunction "PC13_62") (pintype "bidirectional"))
    )
    (net (code "227") (name "unconnected-(DIS1A-PC14-Pad59)") (class "Default")
      (node (ref "DIS1") (pin "59") (pinfunction "PC14_59") (pintype "bidirectional"))
    )
    (net (code "228") (name "unconnected-(DIS1A-PC15-Pad60)") (class "Default")
      (node (ref "DIS1") (pin "60") (pinfunction "PC15_60") (pintype "bidirectional"))
    )
    (net (code "229") (name "unconnected-(DIS1A-PD14-Pad46)") (class "Default")
      (node (ref "DIS1") (pin "46") (pinfunction "PD14_46") (pintype "bidirectional"))
    )
    (net (code "230") (name "unconnected-(DIS1A-PD15-Pad47)") (class "Default")
      (node (ref "DIS1") (pin "47") (pinfunction "PD15_47") (pintype "bidirectional"))
    )
    (net (code "231") (name "unconnected-(DIS1A-PE0-Pad67)") (class "Default")
      (node (ref "DIS1") (pin "67") (pinfunction "PE0_67") (pintype "bidirectional"))
    )
    (net (code "232") (name "unconnected-(DIS1A-PE1-Pad68)") (class "Default")
      (node (ref "DIS1") (pin "68") (pinfunction "PE1_68") (pintype "bidirectional"))
    )
    (net (code "233") (name "unconnected-(DIS1A-PE2-Pad65)") (class "Default")
      (node (ref "DIS1") (pin "65") (pinfunction "PE2_65") (pintype "bidirectional"))
    )
    (net (code "234") (name "unconnected-(DIS1A-PE3-Pad66)") (class "Default")
      (node (ref "DIS1") (pin "66") (pinfunction "PE3_66") (pintype "bidirectional"))
    )
    (net (code "235") (name "unconnected-(DIS1A-PE4-Pad63)") (class "Default")
      (node (ref "DIS1") (pin "63") (pinfunction "PE4_63") (pintype "bidirectional"))
    )
    (net (code "236") (name "unconnected-(DIS1A-PE5-Pad64)") (class "Default")
      (node (ref "DIS1") (pin "64") (pinfunction "PE5_64") (pintype "bidirectional"))
    )
    (net (code "237") (name "unconnected-(DIS1A-PE6-Pad61)") (class "Default")
      (node (ref "DIS1") (pin "61") (pinfunction "PE6_61") (pintype "bidirectional"))
    )
    (net (code "238") (name "unconnected-(DIS1A-PH0-Pad57)") (class "Default")
      (node (ref "DIS1") (pin "57") (pinfunction "PH0_57") (pintype "bidirectional"))
    )
    (net (code "239") (name "unconnected-(DIS1A-PH1-Pad58)") (class "Default")
      (node (ref "DIS1") (pin "58") (pinfunction "PH1_58") (pintype "bidirectional"))
    )
    (net (code "240") (name "unconnected-(ENC_1E-S-Pad5)") (class "Default")
      (node (ref "ENC_1") (pin "5") (pinfunction "S_5") (pintype "passive"))
    )
    (net (code "241") (name "unconnected-(ENC_2E-S-Pad5)") (class "Default")
      (node (ref "ENC_2") (pin "5") (pinfunction "S_5") (pintype "passive"))
    )
    (net (code "242") (name "unconnected-(IC4A-R2IN-Pad8)") (class "Default")
      (node (ref "IC4") (pin "8") (pinfunction "R2IN_8") (pintype "input"))
    )
    (net (code "243") (name "unconnected-(IC4A-R2OUT-Pad9)") (class "Default")
      (node (ref "IC4") (pin "9") (pinfunction "R2OUT_9") (pintype "output"))
    )
    (net (code "244") (name "unconnected-(IC4A-T2IN-Pad10)") (class "Default")
      (node (ref "IC4") (pin "10") (pinfunction "T2IN_10") (pintype "input"))
    )
    (net (code "245") (name "unconnected-(IC4A-T2OUT-Pad7)") (class "Default")
      (node (ref "IC4") (pin "7") (pinfunction "T2OUT_7") (pintype "output"))
    )
    (net (code "246") (name "unconnected-(X1-Pad1)") (class "Default")
      (node (ref "X1") (pin "1") (pinfunction "1_1") (pintype "passive"))
    )
    (net (code "247") (name "unconnected-(X1-Pad7)") (class "Default")
      (node (ref "X1") (pin "7") (pinfunction "7_7") (pintype "passive"))
    )
    (net (code "248") (name "unconnected-(X1-Pad8)") (class "Default")
      (node (ref "X1") (pin "8") (pinfunction "8_8") (pintype "passive"))
    )
    (net (code "249") (name "unconnected-(X1-Pad9)") (class "Default")
      (node (ref "X1") (pin "9") (pinfunction "9_9") (pintype "passive"))
    )
    (net (code "250") (name "unconnected-(XB1-AD0{slash}DIO0-Pad20)") (class "Default")
      (node (ref "XB1") (pin "20") (pinfunction "AD0/DIO0_20") (pintype "bidirectional"))
    )
    (net (code "251") (name "unconnected-(XB1-AD1{slash}DIO1-Pad19)") (class "Default")
      (node (ref "XB1") (pin "19") (pinfunction "AD1/DIO1_19") (pintype "bidirectional"))
    )
    (net (code "252") (name "unconnected-(XB1-AD2{slash}DIO2-Pad18)") (class "Default")
      (node (ref "XB1") (pin "18") (pinfunction "AD2/DIO2_18") (pintype "bidirectional"))
    )
    (net (code "253") (name "unconnected-(XB1-CD{slash}DOUT_EN{slash}DO8-Pad4)") (class "Default")
      (node (ref "XB1") (pin "4") (pinfunction "CD/DOUT_EN/DO8_4") (pintype "output"))
    )
    (net (code "254") (name "unconnected-(XB1-COORD_SEL{slash}AD3{slash}DIO3-Pad17)") (class "Default")
      (node (ref "XB1") (pin "17") (pinfunction "COORD_SEL/AD3/DIO3_17") (pintype "bidirectional"))
    )
    (net (code "255") (name "unconnected-(XB1-ON{slash}~{SLEEP}-Pad13)") (class "Default")
      (node (ref "XB1") (pin "13") (pinfunction "ON/~{SLEEP}_13") (pintype "output"))
    )
    (net (code "256") (name "unconnected-(XB1-RF_TX{slash}AD4{slash}DIO4-Pad11)") (class "Default")
      (node (ref "XB1") (pin "11") (pinfunction "RF_TX/AD4/DIO4_11") (pintype "bidirectional"))
    )
    (net (code "257") (name "unconnected-(XB1-VREF-Pad14)") (class "Default")
      (node (ref "XB1") (pin "14") (pinfunction "VREF_14") (pintype "input"))
    )
    (net (code "258") (name "unconnected-(XB1-~{CTS}{slash}DIO7-Pad12)") (class "Default")
      (node (ref "XB1") (pin "12") (pinfunction "~{CTS}/DIO7_12") (pintype "bidirectional"))
    )
    (net (code "259") (name "unconnected-(XB1-~{DTR}{slash}SLEEP_RQ{slash}DI8-Pad9)") (class "Default")
      (node (ref "XB1") (pin "9") (pinfunction "~{DTR}/SLEEP_RQ/DI8_9") (pintype "bidirectional"))
    )
    (net (code "260") (name "unconnected-(XB1-~{RESET}-Pad5)") (class "Default")
      (node (ref "XB1") (pin "5") (pinfunction "~{RESET}_5") (pintype "input"))
    )
    (net (code "261") (name "unconnected-(XB1-~{RTS}{slash}AD6{slash}DIO6-Pad16)") (class "Default")
      (node (ref "XB1") (pin "16") (pinfunction "~{RTS}/AD6/DIO6_16") (pintype "bidirectional"))
    )
  )
)
